# Public_CPU_Power.net
KiCad netlist of a schematic drawn in Altium Designer
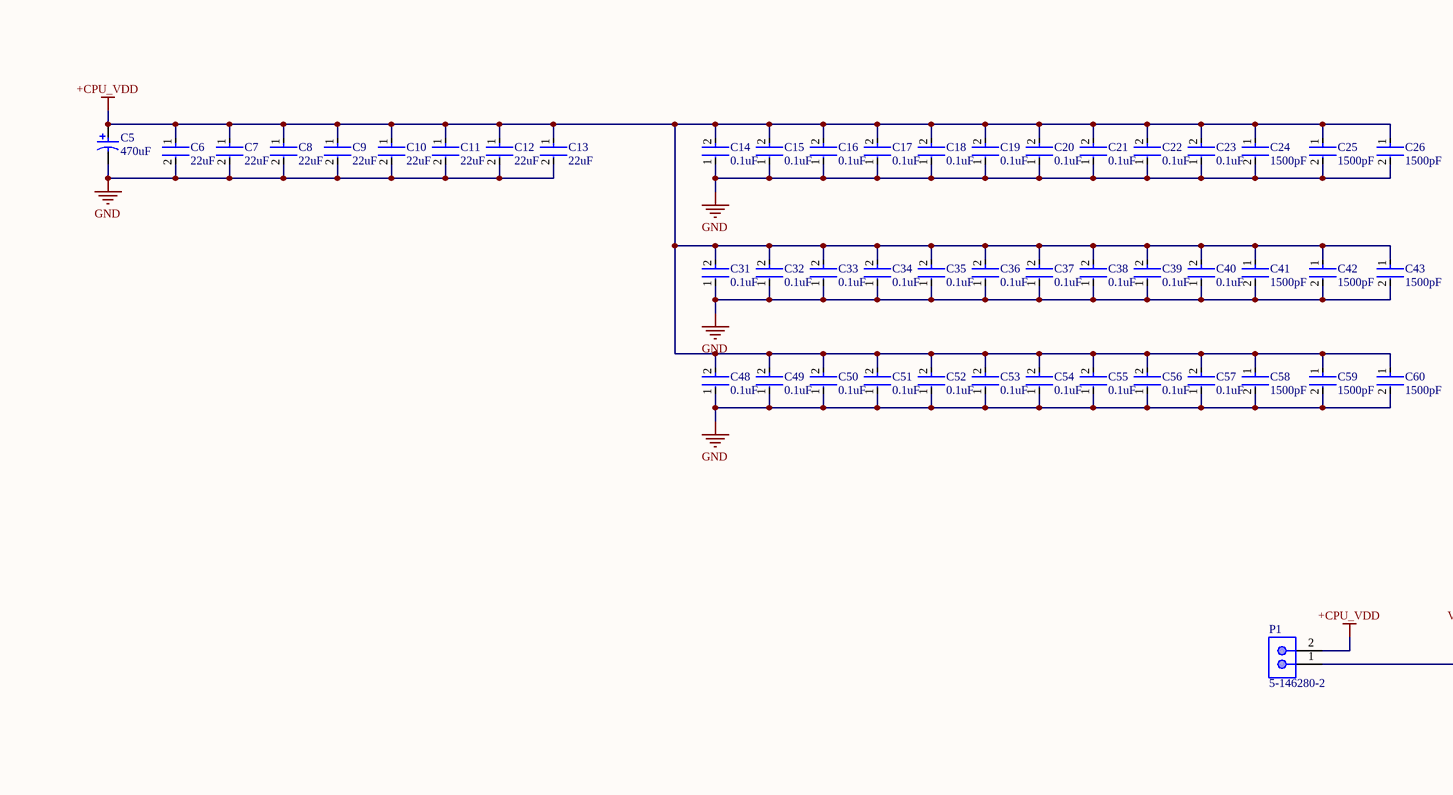
[diagram p0: Public_CPU_Power.SchDoc, top left]
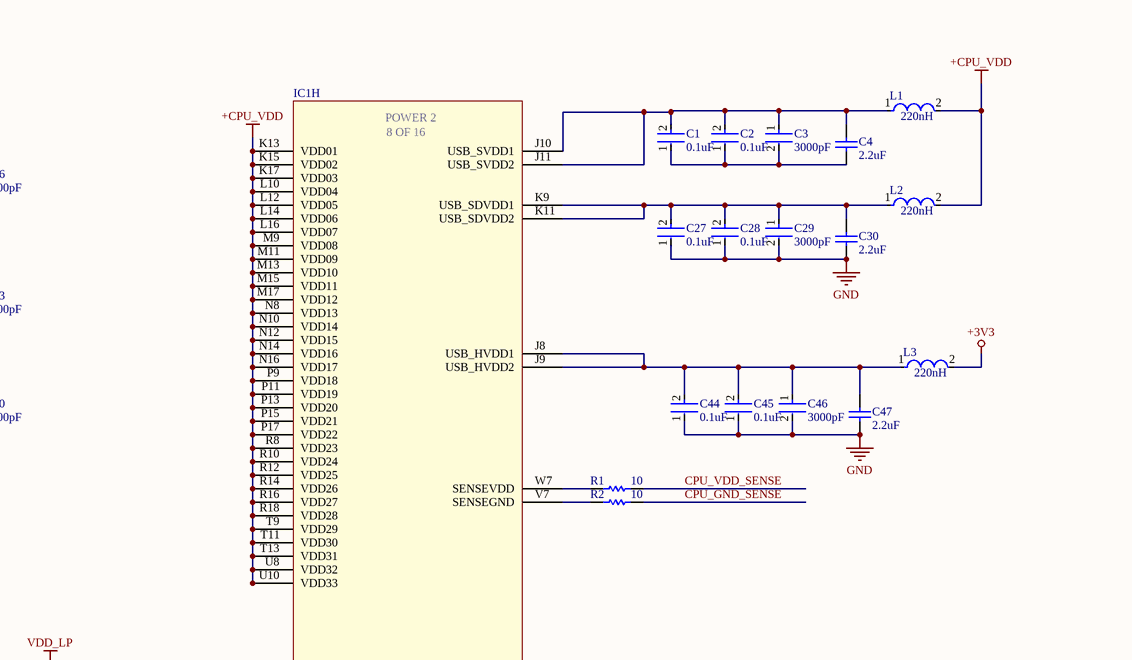
[diagram p1: Public_CPU_Power.SchDoc, top right]
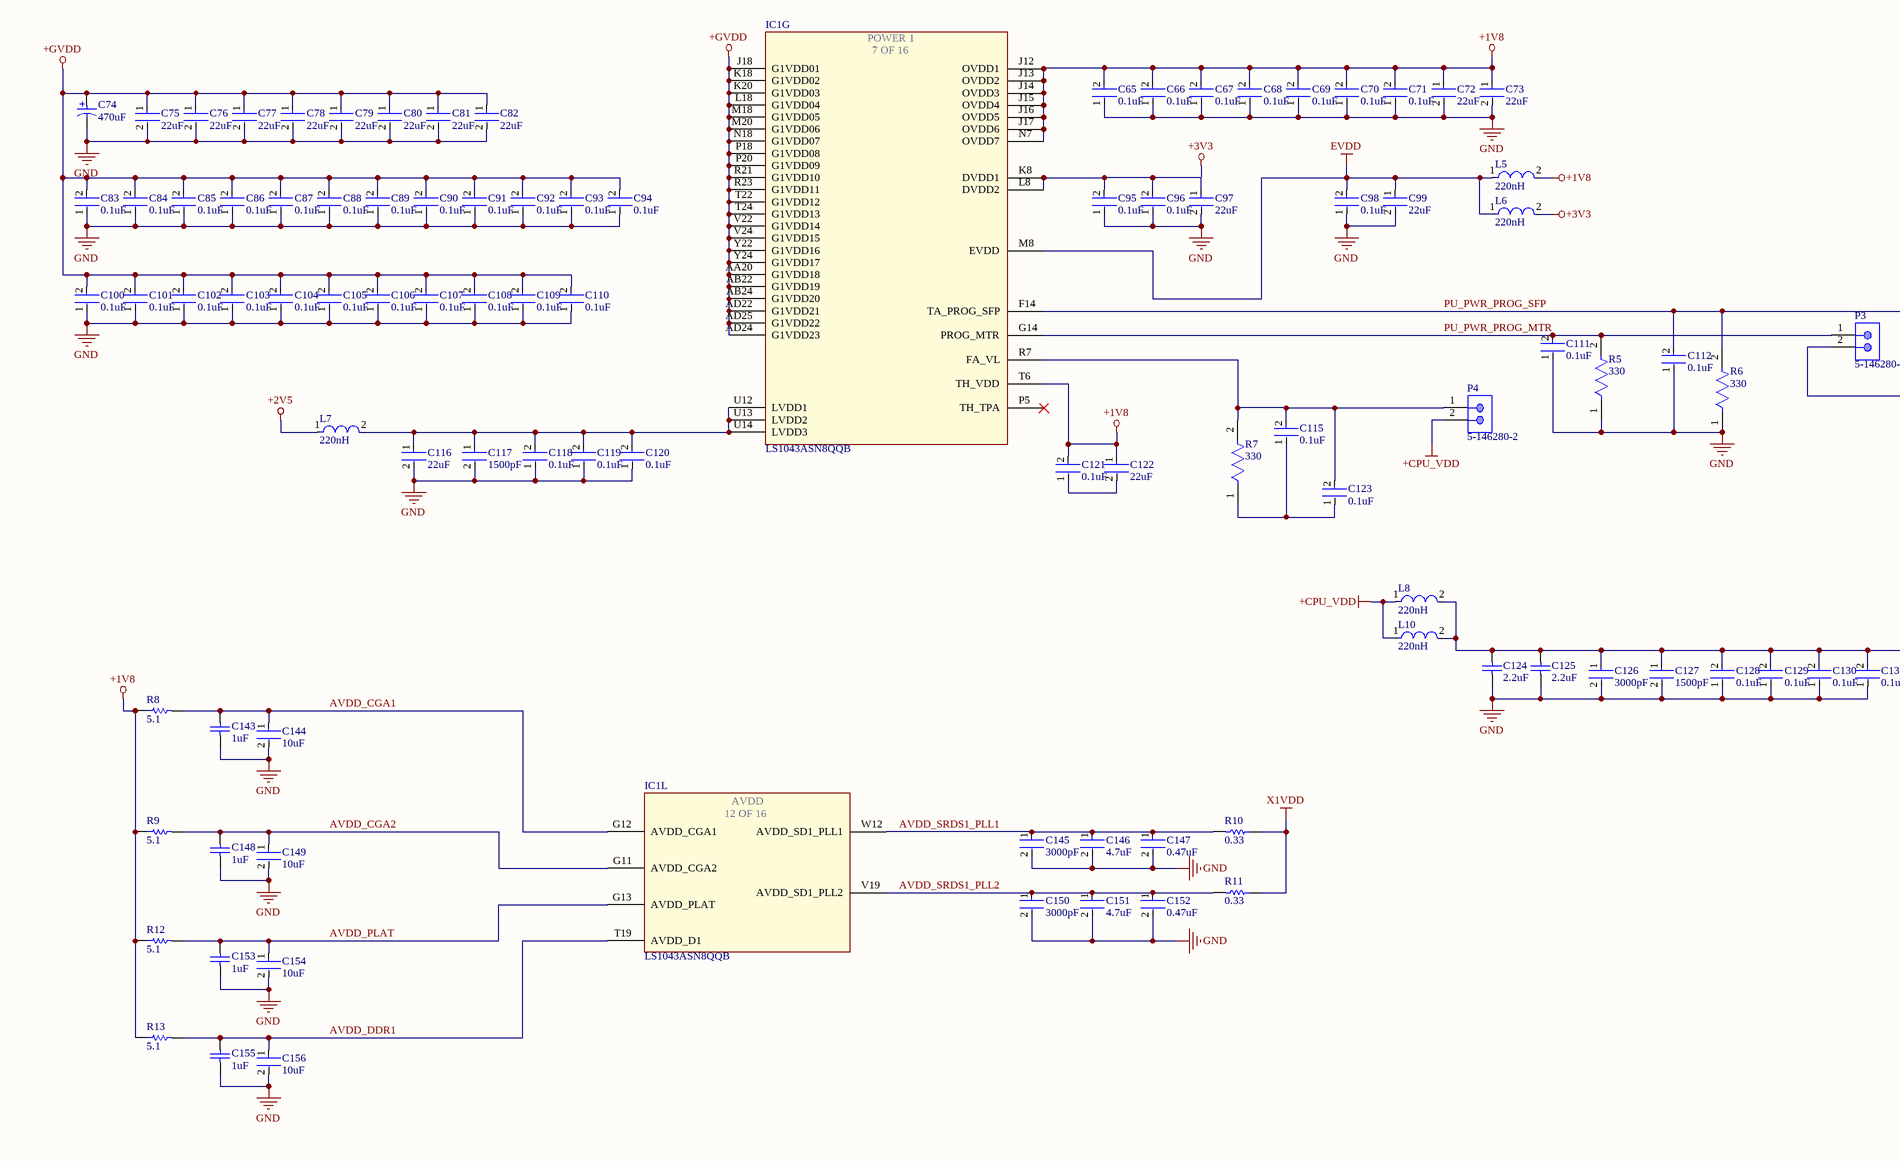
[diagram p2: Public_CPU_Power.SchDoc, bottom left]
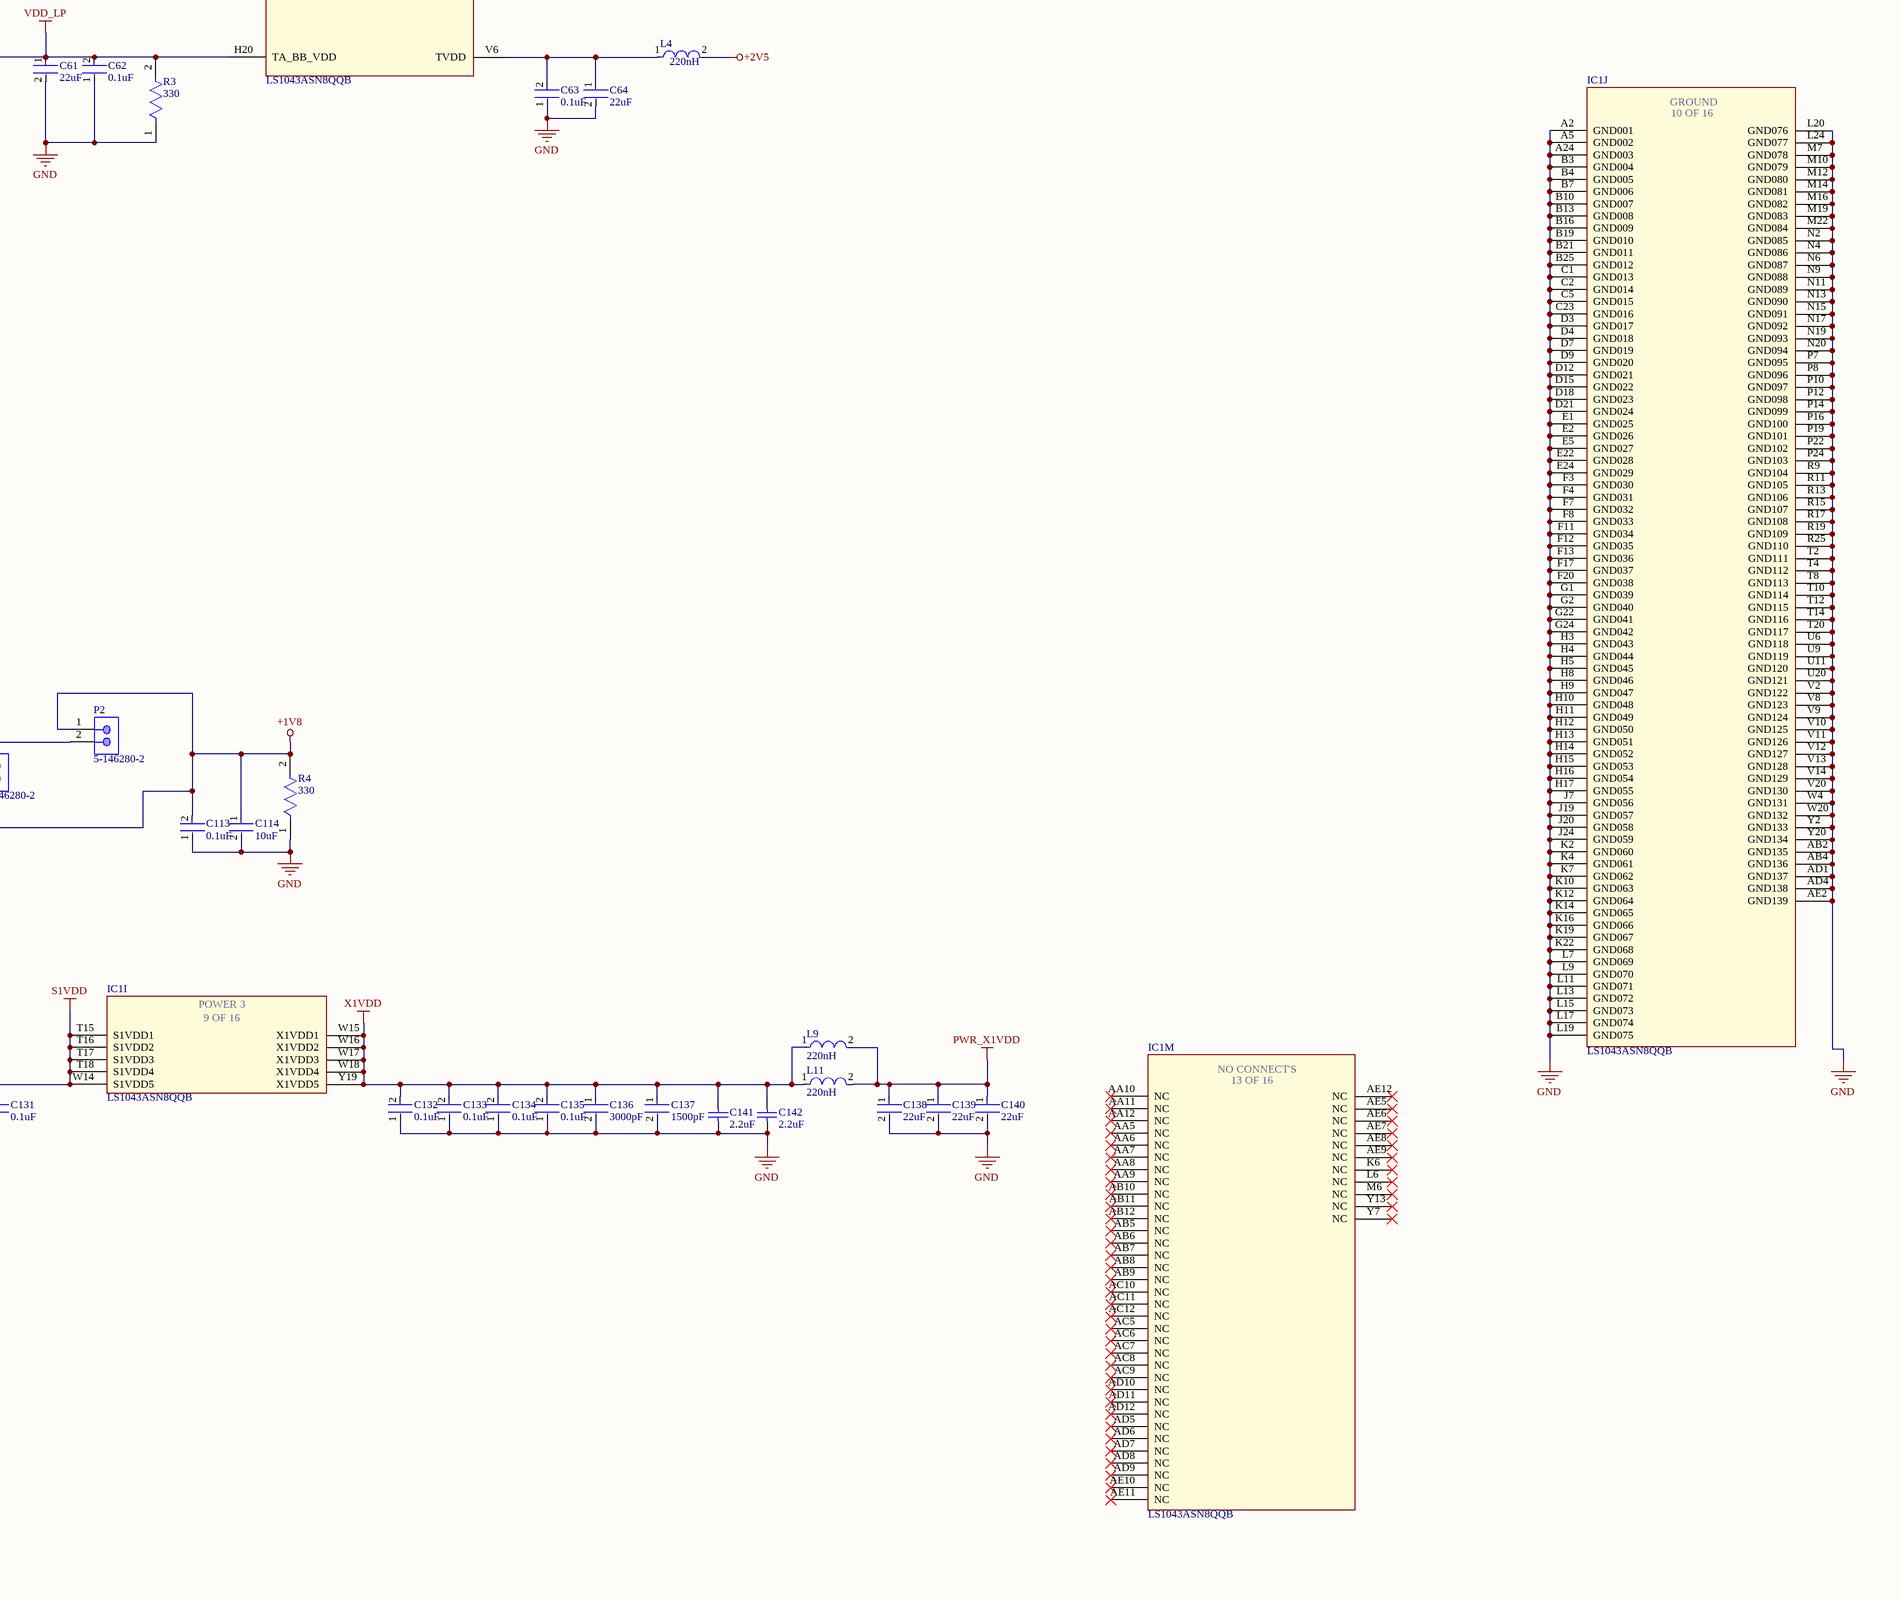
[diagram p3: Public_CPU_Power.SchDoc, bottom right]

(export (version "E")
  (design (tool "Eeschema 10.0.6"))
  (components
    (comp (ref "C1")
      (value "0.1uF")
      (footprint "FP-GRM15-MFG")
      (description "CAP CER 0.1UF 16V X7R 0402")
      (fields (field (name "MANUFACTURER PART NUMBER") "GRM155R71C104KA88D") (field (name "TOLERANCE") "10%"))
      (libsource (lib "Altium Content Vault") (part "236180d848d6139a670b325ea6854c9"))
    )
    (comp (ref "C2")
      (value "0.1uF")
      (footprint "FP-GRM15-MFG")
      (description "CAP CER 0.1UF 16V X7R 0402")
      (fields (field (name "MANUFACTURER PART NUMBER") "GRM155R71C104KA88D") (field (name "TOLERANCE") "10%"))
      (libsource (lib "Altium Content Vault") (part "236180d848d6139a670b325ea6854c9"))
    )
    (comp (ref "C3")
      (value "3000pF")
      (footprint "FP-GRM155-0_05-IPC_B")
      (description "Chip Multilayer Ceramic Capacitors for General Purpose, 0402, 3000pF, U2J, -750ppm/°C, 5%, 10V")
      (fields (field (name "TOLERANCE") "5%"))
      (libsource (lib "Altium Content Vault") (part "02cd4be3c70576c341d710602a673aa"))
    )
    (comp (ref "C4")
      (value "2.2uF")
      (footprint "CAPC1005X55X30NL05T10")
      (fields (field (name "MANUFACTURER") "Kemet") (field (name "PART NUMBER") "C0402C225M9PACTU"))
      (libsource (lib "Altium Content Vault") (part "CAP"))
    )
    (comp (ref "C5")
      (value "470uF")
      (footprint "PNSC-FK-V-F_V")
      (fields (field (name "MANUFACTURER") "Panasonic"))
      (libsource (lib "Altium Content Vault") (part "CAP-P-2"))
    )
    (comp (ref "C6")
      (value "22uF")
      (footprint "FP-GRM21B-0_15-MFG")
      (description "Chip Multilayer Ceramic Capacitors for General Purpose, 0805, 22uF, X5R, 15%, 20%, 6.3V")
      (fields (field (name "VOLTAGE") "6.3V") (field (name "TOLERANCE") "20%"))
      (libsource (lib "Altium Content Vault") (part "b4654b650e69147ec39a6b967a45e02"))
    )
    (comp (ref "C7")
      (value "22uF")
      (footprint "FP-GRM21B-0_15-MFG")
      (description "Chip Multilayer Ceramic Capacitors for General Purpose, 0805, 22uF, X5R, 15%, 20%, 6.3V")
      (fields (field (name "VOLTAGE") "6.3V") (field (name "TOLERANCE") "20%"))
      (libsource (lib "Altium Content Vault") (part "b4654b650e69147ec39a6b967a45e02"))
    )
    (comp (ref "C8")
      (value "22uF")
      (footprint "FP-GRM21B-0_15-MFG")
      (description "Chip Multilayer Ceramic Capacitors for General Purpose, 0805, 22uF, X5R, 15%, 20%, 6.3V")
      (fields (field (name "VOLTAGE") "6.3V") (field (name "TOLERANCE") "20%"))
      (libsource (lib "Altium Content Vault") (part "b4654b650e69147ec39a6b967a45e02"))
    )
    (comp (ref "C9")
      (value "22uF")
      (footprint "FP-GRM21B-0_15-MFG")
      (description "Chip Multilayer Ceramic Capacitors for General Purpose, 0805, 22uF, X5R, 15%, 20%, 6.3V")
      (fields (field (name "VOLTAGE") "6.3V") (field (name "TOLERANCE") "20%"))
      (libsource (lib "Altium Content Vault") (part "b4654b650e69147ec39a6b967a45e02"))
    )
    (comp (ref "C10")
      (value "22uF")
      (footprint "FP-GRM21B-0_15-MFG")
      (description "Chip Multilayer Ceramic Capacitors for General Purpose, 0805, 22uF, X5R, 15%, 20%, 6.3V")
      (fields (field (name "VOLTAGE") "6.3V") (field (name "TOLERANCE") "20%"))
      (libsource (lib "Altium Content Vault") (part "b4654b650e69147ec39a6b967a45e02"))
    )
    (comp (ref "C11")
      (value "22uF")
      (footprint "FP-GRM21B-0_15-MFG")
      (description "Chip Multilayer Ceramic Capacitors for General Purpose, 0805, 22uF, X5R, 15%, 20%, 6.3V")
      (fields (field (name "VOLTAGE") "6.3V") (field (name "TOLERANCE") "20%"))
      (libsource (lib "Altium Content Vault") (part "b4654b650e69147ec39a6b967a45e02"))
    )
    (comp (ref "C12")
      (value "22uF")
      (footprint "FP-GRM21B-0_15-MFG")
      (description "Chip Multilayer Ceramic Capacitors for General Purpose, 0805, 22uF, X5R, 15%, 20%, 6.3V")
      (fields (field (name "VOLTAGE") "6.3V") (field (name "TOLERANCE") "20%"))
      (libsource (lib "Altium Content Vault") (part "b4654b650e69147ec39a6b967a45e02"))
    )
    (comp (ref "C13")
      (value "22uF")
      (footprint "FP-GRM21B-0_15-MFG")
      (description "Chip Multilayer Ceramic Capacitors for General Purpose, 0805, 22uF, X5R, 15%, 20%, 6.3V")
      (fields (field (name "VOLTAGE") "6.3V") (field (name "TOLERANCE") "20%"))
      (libsource (lib "Altium Content Vault") (part "b4654b650e69147ec39a6b967a45e02"))
    )
    (comp (ref "C14")
      (value "0.1uF")
      (footprint "FP-GRM15-MFG")
      (description "CAP CER 0.1UF 16V X7R 0402")
      (fields (field (name "MANUFACTURER PART NUMBER") "GRM155R71C104KA88D") (field (name "TOLERANCE") "10%"))
      (libsource (lib "Altium Content Vault") (part "236180d848d6139a670b325ea6854c9"))
    )
    (comp (ref "C15")
      (value "0.1uF")
      (footprint "FP-GRM15-MFG")
      (description "CAP CER 0.1UF 16V X7R 0402")
      (fields (field (name "MANUFACTURER PART NUMBER") "GRM155R71C104KA88D") (field (name "TOLERANCE") "10%"))
      (libsource (lib "Altium Content Vault") (part "236180d848d6139a670b325ea6854c9"))
    )
    (comp (ref "C16")
      (value "0.1uF")
      (footprint "FP-GRM15-MFG")
      (description "CAP CER 0.1UF 16V X7R 0402")
      (fields (field (name "MANUFACTURER PART NUMBER") "GRM155R71C104KA88D") (field (name "TOLERANCE") "10%"))
      (libsource (lib "Altium Content Vault") (part "236180d848d6139a670b325ea6854c9"))
    )
    (comp (ref "C17")
      (value "0.1uF")
      (footprint "FP-GRM15-MFG")
      (description "CAP CER 0.1UF 16V X7R 0402")
      (fields (field (name "MANUFACTURER PART NUMBER") "GRM155R71C104KA88D") (field (name "TOLERANCE") "10%"))
      (libsource (lib "Altium Content Vault") (part "236180d848d6139a670b325ea6854c9"))
    )
    (comp (ref "C18")
      (value "0.1uF")
      (footprint "FP-GRM15-MFG")
      (description "CAP CER 0.1UF 16V X7R 0402")
      (fields (field (name "MANUFACTURER PART NUMBER") "GRM155R71C104KA88D") (field (name "TOLERANCE") "10%"))
      (libsource (lib "Altium Content Vault") (part "236180d848d6139a670b325ea6854c9"))
    )
    (comp (ref "C19")
      (value "0.1uF")
      (footprint "FP-GRM15-MFG")
      (description "CAP CER 0.1UF 16V X7R 0402")
      (fields (field (name "MANUFACTURER PART NUMBER") "GRM155R71C104KA88D") (field (name "TOLERANCE") "10%"))
      (libsource (lib "Altium Content Vault") (part "236180d848d6139a670b325ea6854c9"))
    )
    (comp (ref "C20")
      (value "0.1uF")
      (footprint "FP-GRM15-MFG")
      (description "CAP CER 0.1UF 16V X7R 0402")
      (fields (field (name "MANUFACTURER PART NUMBER") "GRM155R71C104KA88D") (field (name "TOLERANCE") "10%"))
      (libsource (lib "Altium Content Vault") (part "236180d848d6139a670b325ea6854c9"))
    )
    (comp (ref "C21")
      (value "0.1uF")
      (footprint "FP-GRM15-MFG")
      (description "CAP CER 0.1UF 16V X7R 0402")
      (fields (field (name "MANUFACTURER PART NUMBER") "GRM155R71C104KA88D") (field (name "TOLERANCE") "10%"))
      (libsource (lib "Altium Content Vault") (part "236180d848d6139a670b325ea6854c9"))
    )
    (comp (ref "C22")
      (value "0.1uF")
      (footprint "FP-GRM15-MFG")
      (description "CAP CER 0.1UF 16V X7R 0402")
      (fields (field (name "MANUFACTURER PART NUMBER") "GRM155R71C104KA88D") (field (name "TOLERANCE") "10%"))
      (libsource (lib "Altium Content Vault") (part "236180d848d6139a670b325ea6854c9"))
    )
    (comp (ref "C23")
      (value "0.1uF")
      (footprint "FP-GRM15-MFG")
      (description "CAP CER 0.1UF 16V X7R 0402")
      (fields (field (name "MANUFACTURER PART NUMBER") "GRM155R71C104KA88D") (field (name "TOLERANCE") "10%"))
      (libsource (lib "Altium Content Vault") (part "236180d848d6139a670b325ea6854c9"))
    )
    (comp (ref "C24")
      (value "1500pF")
      (footprint "FP-C0402-BB-MFG")
      (description "CAP CER 1500PF 50V X7R 0402")
      (fields
        (field (name "OCTOPART") "https://octopart.com/c0402c152k5ractu-kemet-125298")
        (field (name "TOLERANCE") "0.1")
      )
      (libsource (lib "Altium Content Vault") (part "b4654b650e69147ec39a6b967a45e02"))
    )
    (comp (ref "C25")
      (value "1500pF")
      (footprint "FP-C0402-BB-MFG")
      (description "CAP CER 1500PF 50V X7R 0402")
      (fields
        (field (name "OCTOPART") "https://octopart.com/c0402c152k5ractu-kemet-125298")
        (field (name "TOLERANCE") "0.1")
      )
      (libsource (lib "Altium Content Vault") (part "b4654b650e69147ec39a6b967a45e02"))
    )
    (comp (ref "C26")
      (value "1500pF")
      (footprint "FP-C0402-BB-MFG")
      (description "CAP CER 1500PF 50V X7R 0402")
      (fields
        (field (name "OCTOPART") "https://octopart.com/c0402c152k5ractu-kemet-125298")
        (field (name "TOLERANCE") "0.1")
      )
      (libsource (lib "Altium Content Vault") (part "b4654b650e69147ec39a6b967a45e02"))
    )
    (comp (ref "C27")
      (value "0.1uF")
      (footprint "FP-GRM15-MFG")
      (description "CAP CER 0.1UF 16V X7R 0402")
      (fields (field (name "MANUFACTURER PART NUMBER") "GRM155R71C104KA88D") (field (name "TOLERANCE") "10%"))
      (libsource (lib "Altium Content Vault") (part "236180d848d6139a670b325ea6854c9"))
    )
    (comp (ref "C28")
      (value "0.1uF")
      (footprint "FP-GRM15-MFG")
      (description "CAP CER 0.1UF 16V X7R 0402")
      (fields (field (name "MANUFACTURER PART NUMBER") "GRM155R71C104KA88D") (field (name "TOLERANCE") "10%"))
      (libsource (lib "Altium Content Vault") (part "236180d848d6139a670b325ea6854c9"))
    )
    (comp (ref "C29")
      (value "3000pF")
      (footprint "FP-GRM155-0_05-IPC_B")
      (description "Chip Multilayer Ceramic Capacitors for General Purpose, 0402, 3000pF, U2J, -750ppm/°C, 5%, 10V")
      (fields (field (name "TOLERANCE") "5%"))
      (libsource (lib "Altium Content Vault") (part "02cd4be3c70576c341d710602a673aa"))
    )
    (comp (ref "C30")
      (value "2.2uF")
      (footprint "CAPC1005X55X30NL05T10")
      (fields (field (name "MANUFACTURER") "Kemet") (field (name "PART NUMBER") "C0402C225M9PACTU"))
      (libsource (lib "Altium Content Vault") (part "CAP"))
    )
    (comp (ref "C31")
      (value "0.1uF")
      (footprint "FP-GRM15-MFG")
      (description "CAP CER 0.1UF 16V X7R 0402")
      (fields (field (name "MANUFACTURER PART NUMBER") "GRM155R71C104KA88D") (field (name "TOLERANCE") "10%"))
      (libsource (lib "Altium Content Vault") (part "236180d848d6139a670b325ea6854c9"))
    )
    (comp (ref "C32")
      (value "0.1uF")
      (footprint "FP-GRM15-MFG")
      (description "CAP CER 0.1UF 16V X7R 0402")
      (fields (field (name "MANUFACTURER PART NUMBER") "GRM155R71C104KA88D") (field (name "TOLERANCE") "10%"))
      (libsource (lib "Altium Content Vault") (part "236180d848d6139a670b325ea6854c9"))
    )
    (comp (ref "C33")
      (value "0.1uF")
      (footprint "FP-GRM15-MFG")
      (description "CAP CER 0.1UF 16V X7R 0402")
      (fields (field (name "MANUFACTURER PART NUMBER") "GRM155R71C104KA88D") (field (name "TOLERANCE") "10%"))
      (libsource (lib "Altium Content Vault") (part "236180d848d6139a670b325ea6854c9"))
    )
    (comp (ref "C34")
      (value "0.1uF")
      (footprint "FP-GRM15-MFG")
      (description "CAP CER 0.1UF 16V X7R 0402")
      (fields (field (name "MANUFACTURER PART NUMBER") "GRM155R71C104KA88D") (field (name "TOLERANCE") "10%"))
      (libsource (lib "Altium Content Vault") (part "236180d848d6139a670b325ea6854c9"))
    )
    (comp (ref "C35")
      (value "0.1uF")
      (footprint "FP-GRM15-MFG")
      (description "CAP CER 0.1UF 16V X7R 0402")
      (fields (field (name "MANUFACTURER PART NUMBER") "GRM155R71C104KA88D") (field (name "TOLERANCE") "10%"))
      (libsource (lib "Altium Content Vault") (part "236180d848d6139a670b325ea6854c9"))
    )
    (comp (ref "C36")
      (value "0.1uF")
      (footprint "FP-GRM15-MFG")
      (description "CAP CER 0.1UF 16V X7R 0402")
      (fields (field (name "MANUFACTURER PART NUMBER") "GRM155R71C104KA88D") (field (name "TOLERANCE") "10%"))
      (libsource (lib "Altium Content Vault") (part "236180d848d6139a670b325ea6854c9"))
    )
    (comp (ref "C37")
      (value "0.1uF")
      (footprint "FP-GRM15-MFG")
      (description "CAP CER 0.1UF 16V X7R 0402")
      (fields (field (name "MANUFACTURER PART NUMBER") "GRM155R71C104KA88D") (field (name "TOLERANCE") "10%"))
      (libsource (lib "Altium Content Vault") (part "236180d848d6139a670b325ea6854c9"))
    )
    (comp (ref "C38")
      (value "0.1uF")
      (footprint "FP-GRM15-MFG")
      (description "CAP CER 0.1UF 16V X7R 0402")
      (fields (field (name "MANUFACTURER PART NUMBER") "GRM155R71C104KA88D") (field (name "TOLERANCE") "10%"))
      (libsource (lib "Altium Content Vault") (part "236180d848d6139a670b325ea6854c9"))
    )
    (comp (ref "C39")
      (value "0.1uF")
      (footprint "FP-GRM15-MFG")
      (description "CAP CER 0.1UF 16V X7R 0402")
      (fields (field (name "MANUFACTURER PART NUMBER") "GRM155R71C104KA88D") (field (name "TOLERANCE") "10%"))
      (libsource (lib "Altium Content Vault") (part "236180d848d6139a670b325ea6854c9"))
    )
    (comp (ref "C40")
      (value "0.1uF")
      (footprint "FP-GRM15-MFG")
      (description "CAP CER 0.1UF 16V X7R 0402")
      (fields (field (name "MANUFACTURER PART NUMBER") "GRM155R71C104KA88D") (field (name "TOLERANCE") "10%"))
      (libsource (lib "Altium Content Vault") (part "236180d848d6139a670b325ea6854c9"))
    )
    (comp (ref "C41")
      (value "1500pF")
      (footprint "FP-C0402-BB-MFG")
      (description "CAP CER 1500PF 50V X7R 0402")
      (fields
        (field (name "OCTOPART") "https://octopart.com/c0402c152k5ractu-kemet-125298")
        (field (name "TOLERANCE") "0.1")
      )
      (libsource (lib "Altium Content Vault") (part "b4654b650e69147ec39a6b967a45e02"))
    )
    (comp (ref "C42")
      (value "1500pF")
      (footprint "FP-C0402-BB-MFG")
      (description "CAP CER 1500PF 50V X7R 0402")
      (fields
        (field (name "OCTOPART") "https://octopart.com/c0402c152k5ractu-kemet-125298")
        (field (name "TOLERANCE") "0.1")
      )
      (libsource (lib "Altium Content Vault") (part "b4654b650e69147ec39a6b967a45e02"))
    )
    (comp (ref "C43")
      (value "1500pF")
      (footprint "FP-C0402-BB-MFG")
      (description "CAP CER 1500PF 50V X7R 0402")
      (fields
        (field (name "OCTOPART") "https://octopart.com/c0402c152k5ractu-kemet-125298")
        (field (name "TOLERANCE") "0.1")
      )
      (libsource (lib "Altium Content Vault") (part "b4654b650e69147ec39a6b967a45e02"))
    )
    (comp (ref "C44")
      (value "0.1uF")
      (footprint "FP-GRM15-MFG")
      (description "CAP CER 0.1UF 16V X7R 0402")
      (fields (field (name "MANUFACTURER PART NUMBER") "GRM155R71C104KA88D") (field (name "TOLERANCE") "10%"))
      (libsource (lib "Altium Content Vault") (part "236180d848d6139a670b325ea6854c9"))
    )
    (comp (ref "C45")
      (value "0.1uF")
      (footprint "FP-GRM15-MFG")
      (description "CAP CER 0.1UF 16V X7R 0402")
      (fields (field (name "MANUFACTURER PART NUMBER") "GRM155R71C104KA88D") (field (name "TOLERANCE") "10%"))
      (libsource (lib "Altium Content Vault") (part "236180d848d6139a670b325ea6854c9"))
    )
    (comp (ref "C46")
      (value "3000pF")
      (footprint "FP-GRM155-0_05-IPC_B")
      (description "Chip Multilayer Ceramic Capacitors for General Purpose, 0402, 3000pF, U2J, -750ppm/°C, 5%, 10V")
      (fields (field (name "TOLERANCE") "5%"))
      (libsource (lib "Altium Content Vault") (part "02cd4be3c70576c341d710602a673aa"))
    )
    (comp (ref "C47")
      (value "2.2uF")
      (footprint "CAPC1005X55X30NL05T10")
      (fields (field (name "MANUFACTURER") "Kemet") (field (name "PART NUMBER") "C0402C225M9PACTU"))
      (libsource (lib "Altium Content Vault") (part "CAP"))
    )
    (comp (ref "C48")
      (value "0.1uF")
      (footprint "FP-GRM15-MFG")
      (description "CAP CER 0.1UF 16V X7R 0402")
      (fields (field (name "MANUFACTURER PART NUMBER") "GRM155R71C104KA88D") (field (name "TOLERANCE") "10%"))
      (libsource (lib "Altium Content Vault") (part "236180d848d6139a670b325ea6854c9"))
    )
    (comp (ref "C49")
      (value "0.1uF")
      (footprint "FP-GRM15-MFG")
      (description "CAP CER 0.1UF 16V X7R 0402")
      (fields (field (name "MANUFACTURER PART NUMBER") "GRM155R71C104KA88D") (field (name "TOLERANCE") "10%"))
      (libsource (lib "Altium Content Vault") (part "236180d848d6139a670b325ea6854c9"))
    )
    (comp (ref "C50")
      (value "0.1uF")
      (footprint "FP-GRM15-MFG")
      (description "CAP CER 0.1UF 16V X7R 0402")
      (fields (field (name "MANUFACTURER PART NUMBER") "GRM155R71C104KA88D") (field (name "TOLERANCE") "10%"))
      (libsource (lib "Altium Content Vault") (part "236180d848d6139a670b325ea6854c9"))
    )
    (comp (ref "C51")
      (value "0.1uF")
      (footprint "FP-GRM15-MFG")
      (description "CAP CER 0.1UF 16V X7R 0402")
      (fields (field (name "MANUFACTURER PART NUMBER") "GRM155R71C104KA88D") (field (name "TOLERANCE") "10%"))
      (libsource (lib "Altium Content Vault") (part "236180d848d6139a670b325ea6854c9"))
    )
    (comp (ref "C52")
      (value "0.1uF")
      (footprint "FP-GRM15-MFG")
      (description "CAP CER 0.1UF 16V X7R 0402")
      (fields (field (name "MANUFACTURER PART NUMBER") "GRM155R71C104KA88D") (field (name "TOLERANCE") "10%"))
      (libsource (lib "Altium Content Vault") (part "236180d848d6139a670b325ea6854c9"))
    )
    (comp (ref "C53")
      (value "0.1uF")
      (footprint "FP-GRM15-MFG")
      (description "CAP CER 0.1UF 16V X7R 0402")
      (fields (field (name "MANUFACTURER PART NUMBER") "GRM155R71C104KA88D") (field (name "TOLERANCE") "10%"))
      (libsource (lib "Altium Content Vault") (part "236180d848d6139a670b325ea6854c9"))
    )
    (comp (ref "C54")
      (value "0.1uF")
      (footprint "FP-GRM15-MFG")
      (description "CAP CER 0.1UF 16V X7R 0402")
      (fields (field (name "MANUFACTURER PART NUMBER") "GRM155R71C104KA88D") (field (name "TOLERANCE") "10%"))
      (libsource (lib "Altium Content Vault") (part "236180d848d6139a670b325ea6854c9"))
    )
    (comp (ref "C55")
      (value "0.1uF")
      (footprint "FP-GRM15-MFG")
      (description "CAP CER 0.1UF 16V X7R 0402")
      (fields (field (name "MANUFACTURER PART NUMBER") "GRM155R71C104KA88D") (field (name "TOLERANCE") "10%"))
      (libsource (lib "Altium Content Vault") (part "236180d848d6139a670b325ea6854c9"))
    )
    (comp (ref "C56")
      (value "0.1uF")
      (footprint "FP-GRM15-MFG")
      (description "CAP CER 0.1UF 16V X7R 0402")
      (fields (field (name "MANUFACTURER PART NUMBER") "GRM155R71C104KA88D") (field (name "TOLERANCE") "10%"))
      (libsource (lib "Altium Content Vault") (part "236180d848d6139a670b325ea6854c9"))
    )
    (comp (ref "C57")
      (value "0.1uF")
      (footprint "FP-GRM15-MFG")
      (description "CAP CER 0.1UF 16V X7R 0402")
      (fields (field (name "MANUFACTURER PART NUMBER") "GRM155R71C104KA88D") (field (name "TOLERANCE") "10%"))
      (libsource (lib "Altium Content Vault") (part "236180d848d6139a670b325ea6854c9"))
    )
    (comp (ref "C58")
      (value "1500pF")
      (footprint "FP-C0402-BB-MFG")
      (description "CAP CER 1500PF 50V X7R 0402")
      (fields
        (field (name "OCTOPART") "https://octopart.com/c0402c152k5ractu-kemet-125298")
        (field (name "TOLERANCE") "0.1")
      )
      (libsource (lib "Altium Content Vault") (part "b4654b650e69147ec39a6b967a45e02"))
    )
    (comp (ref "C59")
      (value "1500pF")
      (footprint "FP-C0402-BB-MFG")
      (description "CAP CER 1500PF 50V X7R 0402")
      (fields
        (field (name "OCTOPART") "https://octopart.com/c0402c152k5ractu-kemet-125298")
        (field (name "TOLERANCE") "0.1")
      )
      (libsource (lib "Altium Content Vault") (part "b4654b650e69147ec39a6b967a45e02"))
    )
    (comp (ref "C60")
      (value "1500pF")
      (footprint "FP-C0402-BB-MFG")
      (description "CAP CER 1500PF 50V X7R 0402")
      (fields
        (field (name "OCTOPART") "https://octopart.com/c0402c152k5ractu-kemet-125298")
        (field (name "TOLERANCE") "0.1")
      )
      (libsource (lib "Altium Content Vault") (part "b4654b650e69147ec39a6b967a45e02"))
    )
    (comp (ref "C61")
      (value "22uF")
      (footprint "FP-GRM21B-0_15-MFG")
      (description "Chip Multilayer Ceramic Capacitors for General Purpose, 0805, 22uF, X5R, 15%, 20%, 6.3V")
      (fields (field (name "VOLTAGE") "6.3V") (field (name "TOLERANCE") "20%"))
      (libsource (lib "Altium Content Vault") (part "b4654b650e69147ec39a6b967a45e02"))
    )
    (comp (ref "C62")
      (value "0.1uF")
      (footprint "FP-GRM15-MFG")
      (description "CAP CER 0.1UF 16V X7R 0402")
      (fields (field (name "MANUFACTURER PART NUMBER") "GRM155R71C104KA88D") (field (name "TOLERANCE") "10%"))
      (libsource (lib "Altium Content Vault") (part "236180d848d6139a670b325ea6854c9"))
    )
    (comp (ref "C63")
      (value "0.1uF")
      (footprint "FP-GRM15-MFG")
      (description "CAP CER 0.1UF 16V X7R 0402")
      (fields (field (name "MANUFACTURER PART NUMBER") "GRM155R71C104KA88D") (field (name "TOLERANCE") "10%"))
      (libsource (lib "Altium Content Vault") (part "236180d848d6139a670b325ea6854c9"))
    )
    (comp (ref "C64")
      (value "22uF")
      (footprint "FP-GRM21B-0_15-MFG")
      (description "Chip Multilayer Ceramic Capacitors for General Purpose, 0805, 22uF, X5R, 15%, 20%, 6.3V")
      (fields (field (name "VOLTAGE") "6.3V") (field (name "TOLERANCE") "20%"))
      (libsource (lib "Altium Content Vault") (part "b4654b650e69147ec39a6b967a45e02"))
    )
    (comp (ref "C65")
      (value "0.1uF")
      (footprint "FP-GRM15-MFG")
      (description "CAP CER 0.1UF 16V X7R 0402")
      (fields (field (name "MANUFACTURER PART NUMBER") "GRM155R71C104KA88D") (field (name "TOLERANCE") "10%"))
      (libsource (lib "Altium Content Vault") (part "236180d848d6139a670b325ea6854c9"))
    )
    (comp (ref "C66")
      (value "0.1uF")
      (footprint "FP-GRM15-MFG")
      (description "CAP CER 0.1UF 16V X7R 0402")
      (fields (field (name "MANUFACTURER PART NUMBER") "GRM155R71C104KA88D") (field (name "TOLERANCE") "10%"))
      (libsource (lib "Altium Content Vault") (part "236180d848d6139a670b325ea6854c9"))
    )
    (comp (ref "C67")
      (value "0.1uF")
      (footprint "FP-GRM15-MFG")
      (description "CAP CER 0.1UF 16V X7R 0402")
      (fields (field (name "MANUFACTURER PART NUMBER") "GRM155R71C104KA88D") (field (name "TOLERANCE") "10%"))
      (libsource (lib "Altium Content Vault") (part "236180d848d6139a670b325ea6854c9"))
    )
    (comp (ref "C68")
      (value "0.1uF")
      (footprint "FP-GRM15-MFG")
      (description "CAP CER 0.1UF 16V X7R 0402")
      (fields (field (name "MANUFACTURER PART NUMBER") "GRM155R71C104KA88D") (field (name "TOLERANCE") "10%"))
      (libsource (lib "Altium Content Vault") (part "236180d848d6139a670b325ea6854c9"))
    )
    (comp (ref "C69")
      (value "0.1uF")
      (footprint "FP-GRM15-MFG")
      (description "CAP CER 0.1UF 16V X7R 0402")
      (fields (field (name "MANUFACTURER PART NUMBER") "GRM155R71C104KA88D") (field (name "TOLERANCE") "10%"))
      (libsource (lib "Altium Content Vault") (part "236180d848d6139a670b325ea6854c9"))
    )
    (comp (ref "C70")
      (value "0.1uF")
      (footprint "FP-GRM15-MFG")
      (description "CAP CER 0.1UF 16V X7R 0402")
      (fields (field (name "MANUFACTURER PART NUMBER") "GRM155R71C104KA88D") (field (name "TOLERANCE") "10%"))
      (libsource (lib "Altium Content Vault") (part "236180d848d6139a670b325ea6854c9"))
    )
    (comp (ref "C71")
      (value "0.1uF")
      (footprint "FP-GRM15-MFG")
      (description "CAP CER 0.1UF 16V X7R 0402")
      (fields (field (name "MANUFACTURER PART NUMBER") "GRM155R71C104KA88D") (field (name "TOLERANCE") "10%"))
      (libsource (lib "Altium Content Vault") (part "236180d848d6139a670b325ea6854c9"))
    )
    (comp (ref "C72")
      (value "22uF")
      (footprint "FP-GRM21B-0_15-MFG")
      (description "Chip Multilayer Ceramic Capacitors for General Purpose, 0805, 22uF, X5R, 15%, 20%, 6.3V")
      (fields (field (name "VOLTAGE") "6.3V") (field (name "TOLERANCE") "20%"))
      (libsource (lib "Altium Content Vault") (part "b4654b650e69147ec39a6b967a45e02"))
    )
    (comp (ref "C73")
      (value "22uF")
      (footprint "FP-GRM21B-0_15-MFG")
      (description "Chip Multilayer Ceramic Capacitors for General Purpose, 0805, 22uF, X5R, 15%, 20%, 6.3V")
      (fields (field (name "VOLTAGE") "6.3V") (field (name "TOLERANCE") "20%"))
      (libsource (lib "Altium Content Vault") (part "b4654b650e69147ec39a6b967a45e02"))
    )
    (comp (ref "C74")
      (value "470uF")
      (footprint "PNSC-FK-V-F_V")
      (fields (field (name "MANUFACTURER") "Panasonic"))
      (libsource (lib "Altium Content Vault") (part "CAP-P-2"))
    )
    (comp (ref "C75")
      (value "22uF")
      (footprint "FP-GRM21B-0_15-MFG")
      (description "Chip Multilayer Ceramic Capacitors for General Purpose, 0805, 22uF, X5R, 15%, 20%, 6.3V")
      (fields (field (name "VOLTAGE") "6.3V") (field (name "TOLERANCE") "20%"))
      (libsource (lib "Altium Content Vault") (part "b4654b650e69147ec39a6b967a45e02"))
    )
    (comp (ref "C76")
      (value "22uF")
      (footprint "FP-GRM21B-0_15-MFG")
      (description "Chip Multilayer Ceramic Capacitors for General Purpose, 0805, 22uF, X5R, 15%, 20%, 6.3V")
      (fields (field (name "VOLTAGE") "6.3V") (field (name "TOLERANCE") "20%"))
      (libsource (lib "Altium Content Vault") (part "b4654b650e69147ec39a6b967a45e02"))
    )
    (comp (ref "C77")
      (value "22uF")
      (footprint "FP-GRM21B-0_15-MFG")
      (description "Chip Multilayer Ceramic Capacitors for General Purpose, 0805, 22uF, X5R, 15%, 20%, 6.3V")
      (fields (field (name "VOLTAGE") "6.3V") (field (name "TOLERANCE") "20%"))
      (libsource (lib "Altium Content Vault") (part "b4654b650e69147ec39a6b967a45e02"))
    )
    (comp (ref "C78")
      (value "22uF")
      (footprint "FP-GRM21B-0_15-MFG")
      (description "Chip Multilayer Ceramic Capacitors for General Purpose, 0805, 22uF, X5R, 15%, 20%, 6.3V")
      (fields (field (name "VOLTAGE") "6.3V") (field (name "TOLERANCE") "20%"))
      (libsource (lib "Altium Content Vault") (part "b4654b650e69147ec39a6b967a45e02"))
    )
    (comp (ref "C79")
      (value "22uF")
      (footprint "FP-GRM21B-0_15-MFG")
      (description "Chip Multilayer Ceramic Capacitors for General Purpose, 0805, 22uF, X5R, 15%, 20%, 6.3V")
      (fields (field (name "VOLTAGE") "6.3V") (field (name "TOLERANCE") "20%"))
      (libsource (lib "Altium Content Vault") (part "b4654b650e69147ec39a6b967a45e02"))
    )
    (comp (ref "C80")
      (value "22uF")
      (footprint "FP-GRM21B-0_15-MFG")
      (description "Chip Multilayer Ceramic Capacitors for General Purpose, 0805, 22uF, X5R, 15%, 20%, 6.3V")
      (fields (field (name "VOLTAGE") "6.3V") (field (name "TOLERANCE") "20%"))
      (libsource (lib "Altium Content Vault") (part "b4654b650e69147ec39a6b967a45e02"))
    )
    (comp (ref "C81")
      (value "22uF")
      (footprint "FP-GRM21B-0_15-MFG")
      (description "Chip Multilayer Ceramic Capacitors for General Purpose, 0805, 22uF, X5R, 15%, 20%, 6.3V")
      (fields (field (name "VOLTAGE") "6.3V") (field (name "TOLERANCE") "20%"))
      (libsource (lib "Altium Content Vault") (part "b4654b650e69147ec39a6b967a45e02"))
    )
    (comp (ref "C82")
      (value "22uF")
      (footprint "FP-GRM21B-0_15-MFG")
      (description "Chip Multilayer Ceramic Capacitors for General Purpose, 0805, 22uF, X5R, 15%, 20%, 6.3V")
      (fields (field (name "VOLTAGE") "6.3V") (field (name "TOLERANCE") "20%"))
      (libsource (lib "Altium Content Vault") (part "b4654b650e69147ec39a6b967a45e02"))
    )
    (comp (ref "C83")
      (value "0.1uF")
      (footprint "FP-GRM15-MFG")
      (description "CAP CER 0.1UF 16V X7R 0402")
      (fields (field (name "MANUFACTURER PART NUMBER") "GRM155R71C104KA88D") (field (name "TOLERANCE") "10%"))
      (libsource (lib "Altium Content Vault") (part "236180d848d6139a670b325ea6854c9"))
    )
    (comp (ref "C84")
      (value "0.1uF")
      (footprint "FP-GRM15-MFG")
      (description "CAP CER 0.1UF 16V X7R 0402")
      (fields (field (name "MANUFACTURER PART NUMBER") "GRM155R71C104KA88D") (field (name "TOLERANCE") "10%"))
      (libsource (lib "Altium Content Vault") (part "236180d848d6139a670b325ea6854c9"))
    )
    (comp (ref "C85")
      (value "0.1uF")
      (footprint "FP-GRM15-MFG")
      (description "CAP CER 0.1UF 16V X7R 0402")
      (fields (field (name "MANUFACTURER PART NUMBER") "GRM155R71C104KA88D") (field (name "TOLERANCE") "10%"))
      (libsource (lib "Altium Content Vault") (part "236180d848d6139a670b325ea6854c9"))
    )
    (comp (ref "C86")
      (value "0.1uF")
      (footprint "FP-GRM15-MFG")
      (description "CAP CER 0.1UF 16V X7R 0402")
      (fields (field (name "MANUFACTURER PART NUMBER") "GRM155R71C104KA88D") (field (name "TOLERANCE") "10%"))
      (libsource (lib "Altium Content Vault") (part "236180d848d6139a670b325ea6854c9"))
    )
    (comp (ref "C87")
      (value "0.1uF")
      (footprint "FP-GRM15-MFG")
      (description "CAP CER 0.1UF 16V X7R 0402")
      (fields (field (name "MANUFACTURER PART NUMBER") "GRM155R71C104KA88D") (field (name "TOLERANCE") "10%"))
      (libsource (lib "Altium Content Vault") (part "236180d848d6139a670b325ea6854c9"))
    )
    (comp (ref "C88")
      (value "0.1uF")
      (footprint "FP-GRM15-MFG")
      (description "CAP CER 0.1UF 16V X7R 0402")
      (fields (field (name "MANUFACTURER PART NUMBER") "GRM155R71C104KA88D") (field (name "TOLERANCE") "10%"))
      (libsource (lib "Altium Content Vault") (part "236180d848d6139a670b325ea6854c9"))
    )
    (comp (ref "C89")
      (value "0.1uF")
      (footprint "FP-GRM15-MFG")
      (description "CAP CER 0.1UF 16V X7R 0402")
      (fields (field (name "MANUFACTURER PART NUMBER") "GRM155R71C104KA88D") (field (name "TOLERANCE") "10%"))
      (libsource (lib "Altium Content Vault") (part "236180d848d6139a670b325ea6854c9"))
    )
    (comp (ref "C90")
      (value "0.1uF")
      (footprint "FP-GRM15-MFG")
      (description "CAP CER 0.1UF 16V X7R 0402")
      (fields (field (name "MANUFACTURER PART NUMBER") "GRM155R71C104KA88D") (field (name "TOLERANCE") "10%"))
      (libsource (lib "Altium Content Vault") (part "236180d848d6139a670b325ea6854c9"))
    )
    (comp (ref "C91")
      (value "0.1uF")
      (footprint "FP-GRM15-MFG")
      (description "CAP CER 0.1UF 16V X7R 0402")
      (fields (field (name "MANUFACTURER PART NUMBER") "GRM155R71C104KA88D") (field (name "TOLERANCE") "10%"))
      (libsource (lib "Altium Content Vault") (part "236180d848d6139a670b325ea6854c9"))
    )
    (comp (ref "C92")
      (value "0.1uF")
      (footprint "FP-GRM15-MFG")
      (description "CAP CER 0.1UF 16V X7R 0402")
      (fields (field (name "MANUFACTURER PART NUMBER") "GRM155R71C104KA88D") (field (name "TOLERANCE") "10%"))
      (libsource (lib "Altium Content Vault") (part "236180d848d6139a670b325ea6854c9"))
    )
    (comp (ref "C93")
      (value "0.1uF")
      (footprint "FP-GRM15-MFG")
      (description "CAP CER 0.1UF 16V X7R 0402")
      (fields (field (name "MANUFACTURER PART NUMBER") "GRM155R71C104KA88D") (field (name "TOLERANCE") "10%"))
      (libsource (lib "Altium Content Vault") (part "236180d848d6139a670b325ea6854c9"))
    )
    (comp (ref "C94")
      (value "0.1uF")
      (footprint "FP-GRM15-MFG")
      (description "CAP CER 0.1UF 16V X7R 0402")
      (fields (field (name "MANUFACTURER PART NUMBER") "GRM155R71C104KA88D") (field (name "TOLERANCE") "10%"))
      (libsource (lib "Altium Content Vault") (part "236180d848d6139a670b325ea6854c9"))
    )
    (comp (ref "C95")
      (value "0.1uF")
      (footprint "FP-GRM15-MFG")
      (description "CAP CER 0.1UF 16V X7R 0402")
      (fields (field (name "MANUFACTURER PART NUMBER") "GRM155R71C104KA88D") (field (name "TOLERANCE") "10%"))
      (libsource (lib "Altium Content Vault") (part "236180d848d6139a670b325ea6854c9"))
    )
    (comp (ref "C96")
      (value "0.1uF")
      (footprint "FP-GRM15-MFG")
      (description "CAP CER 0.1UF 16V X7R 0402")
      (fields (field (name "MANUFACTURER PART NUMBER") "GRM155R71C104KA88D") (field (name "TOLERANCE") "10%"))
      (libsource (lib "Altium Content Vault") (part "236180d848d6139a670b325ea6854c9"))
    )
    (comp (ref "C97")
      (value "22uF")
      (footprint "FP-GRM21B-0_15-MFG")
      (description "Chip Multilayer Ceramic Capacitors for General Purpose, 0805, 22uF, X5R, 15%, 20%, 6.3V")
      (fields (field (name "VOLTAGE") "6.3V") (field (name "TOLERANCE") "20%"))
      (libsource (lib "Altium Content Vault") (part "b4654b650e69147ec39a6b967a45e02"))
    )
    (comp (ref "C98")
      (value "0.1uF")
      (footprint "FP-GRM15-MFG")
      (description "CAP CER 0.1UF 16V X7R 0402")
      (fields (field (name "MANUFACTURER PART NUMBER") "GRM155R71C104KA88D") (field (name "TOLERANCE") "10%"))
      (libsource (lib "Altium Content Vault") (part "236180d848d6139a670b325ea6854c9"))
    )
    (comp (ref "C99")
      (value "22uF")
      (footprint "FP-GRM21B-0_15-MFG")
      (description "Chip Multilayer Ceramic Capacitors for General Purpose, 0805, 22uF, X5R, 15%, 20%, 6.3V")
      (fields (field (name "VOLTAGE") "6.3V") (field (name "TOLERANCE") "20%"))
      (libsource (lib "Altium Content Vault") (part "b4654b650e69147ec39a6b967a45e02"))
    )
    (comp (ref "C100")
      (value "0.1uF")
      (footprint "FP-GRM15-MFG")
      (description "CAP CER 0.1UF 16V X7R 0402")
      (fields (field (name "MANUFACTURER PART NUMBER") "GRM155R71C104KA88D") (field (name "TOLERANCE") "10%"))
      (libsource (lib "Altium Content Vault") (part "236180d848d6139a670b325ea6854c9"))
    )
    (comp (ref "C101")
      (value "0.1uF")
      (footprint "FP-GRM15-MFG")
      (description "CAP CER 0.1UF 16V X7R 0402")
      (fields (field (name "MANUFACTURER PART NUMBER") "GRM155R71C104KA88D") (field (name "TOLERANCE") "10%"))
      (libsource (lib "Altium Content Vault") (part "236180d848d6139a670b325ea6854c9"))
    )
    (comp (ref "C102")
      (value "0.1uF")
      (footprint "FP-GRM15-MFG")
      (description "CAP CER 0.1UF 16V X7R 0402")
      (fields (field (name "MANUFACTURER PART NUMBER") "GRM155R71C104KA88D") (field (name "TOLERANCE") "10%"))
      (libsource (lib "Altium Content Vault") (part "236180d848d6139a670b325ea6854c9"))
    )
    (comp (ref "C103")
      (value "0.1uF")
      (footprint "FP-GRM15-MFG")
      (description "CAP CER 0.1UF 16V X7R 0402")
      (fields (field (name "MANUFACTURER PART NUMBER") "GRM155R71C104KA88D") (field (name "TOLERANCE") "10%"))
      (libsource (lib "Altium Content Vault") (part "236180d848d6139a670b325ea6854c9"))
    )
    (comp (ref "C104")
      (value "0.1uF")
      (footprint "FP-GRM15-MFG")
      (description "CAP CER 0.1UF 16V X7R 0402")
      (fields (field (name "MANUFACTURER PART NUMBER") "GRM155R71C104KA88D") (field (name "TOLERANCE") "10%"))
      (libsource (lib "Altium Content Vault") (part "236180d848d6139a670b325ea6854c9"))
    )
    (comp (ref "C105")
      (value "0.1uF")
      (footprint "FP-GRM15-MFG")
      (description "CAP CER 0.1UF 16V X7R 0402")
      (fields (field (name "MANUFACTURER PART NUMBER") "GRM155R71C104KA88D") (field (name "TOLERANCE") "10%"))
      (libsource (lib "Altium Content Vault") (part "236180d848d6139a670b325ea6854c9"))
    )
    (comp (ref "C106")
      (value "0.1uF")
      (footprint "FP-GRM15-MFG")
      (description "CAP CER 0.1UF 16V X7R 0402")
      (fields (field (name "MANUFACTURER PART NUMBER") "GRM155R71C104KA88D") (field (name "TOLERANCE") "10%"))
      (libsource (lib "Altium Content Vault") (part "236180d848d6139a670b325ea6854c9"))
    )
    (comp (ref "C107")
      (value "0.1uF")
      (footprint "FP-GRM15-MFG")
      (description "CAP CER 0.1UF 16V X7R 0402")
      (fields (field (name "MANUFACTURER PART NUMBER") "GRM155R71C104KA88D") (field (name "TOLERANCE") "10%"))
      (libsource (lib "Altium Content Vault") (part "236180d848d6139a670b325ea6854c9"))
    )
    (comp (ref "C108")
      (value "0.1uF")
      (footprint "FP-GRM15-MFG")
      (description "CAP CER 0.1UF 16V X7R 0402")
      (fields (field (name "MANUFACTURER PART NUMBER") "GRM155R71C104KA88D") (field (name "TOLERANCE") "10%"))
      (libsource (lib "Altium Content Vault") (part "236180d848d6139a670b325ea6854c9"))
    )
    (comp (ref "C109")
      (value "0.1uF")
      (footprint "FP-GRM15-MFG")
      (description "CAP CER 0.1UF 16V X7R 0402")
      (fields (field (name "MANUFACTURER PART NUMBER") "GRM155R71C104KA88D") (field (name "TOLERANCE") "10%"))
      (libsource (lib "Altium Content Vault") (part "236180d848d6139a670b325ea6854c9"))
    )
    (comp (ref "C110")
      (value "0.1uF")
      (footprint "FP-GRM15-MFG")
      (description "CAP CER 0.1UF 16V X7R 0402")
      (fields (field (name "MANUFACTURER PART NUMBER") "GRM155R71C104KA88D") (field (name "TOLERANCE") "10%"))
      (libsource (lib "Altium Content Vault") (part "236180d848d6139a670b325ea6854c9"))
    )
    (comp (ref "C111")
      (value "0.1uF")
      (footprint "FP-GRM15-MFG")
      (description "CAP CER 0.1UF 16V X7R 0402")
      (fields (field (name "MANUFACTURER PART NUMBER") "GRM155R71C104KA88D") (field (name "TOLERANCE") "10%"))
      (libsource (lib "Altium Content Vault") (part "236180d848d6139a670b325ea6854c9"))
    )
    (comp (ref "C112")
      (value "0.1uF")
      (footprint "FP-GRM15-MFG")
      (description "CAP CER 0.1UF 16V X7R 0402")
      (fields (field (name "MANUFACTURER PART NUMBER") "GRM155R71C104KA88D") (field (name "TOLERANCE") "10%"))
      (libsource (lib "Altium Content Vault") (part "236180d848d6139a670b325ea6854c9"))
    )
    (comp (ref "C113")
      (value "0.1uF")
      (footprint "FP-GRM15-MFG")
      (description "CAP CER 0.1UF 16V X7R 0402")
      (fields (field (name "MANUFACTURER PART NUMBER") "GRM155R71C104KA88D") (field (name "TOLERANCE") "10%"))
      (libsource (lib "Altium Content Vault") (part "236180d848d6139a670b325ea6854c9"))
    )
    (comp (ref "C114")
      (value "10uF")
      (footprint "FP-C0805C-DG-MFG")
      (description "CAP CER 10UF 10V X5R 0805")
      (fields (field (name "TOLERANCE") "10%") (field (name "MANUFACTURER PART NUMBER") "C0805C106K8PACTU"))
      (libsource (lib "Altium Content Vault") (part "11868f565c42a9108669ba33697ecf6"))
    )
    (comp (ref "C115")
      (value "0.1uF")
      (footprint "FP-GRM15-MFG")
      (description "CAP CER 0.1UF 16V X7R 0402")
      (fields (field (name "MANUFACTURER PART NUMBER") "GRM155R71C104KA88D") (field (name "TOLERANCE") "10%"))
      (libsource (lib "Altium Content Vault") (part "236180d848d6139a670b325ea6854c9"))
    )
    (comp (ref "C116")
      (value "22uF")
      (footprint "FP-GRM21B-0_15-MFG")
      (description "Chip Multilayer Ceramic Capacitors for General Purpose, 0805, 22uF, X5R, 15%, 20%, 6.3V")
      (fields (field (name "VOLTAGE") "6.3V") (field (name "TOLERANCE") "20%"))
      (libsource (lib "Altium Content Vault") (part "b4654b650e69147ec39a6b967a45e02"))
    )
    (comp (ref "C117")
      (value "1500pF")
      (footprint "FP-C0402-BB-MFG")
      (description "CAP CER 1500PF 50V X7R 0402")
      (fields
        (field (name "OCTOPART") "https://octopart.com/c0402c152k5ractu-kemet-125298")
        (field (name "TOLERANCE") "0.1")
      )
      (libsource (lib "Altium Content Vault") (part "b4654b650e69147ec39a6b967a45e02"))
    )
    (comp (ref "C118")
      (value "0.1uF")
      (footprint "FP-GRM15-MFG")
      (description "CAP CER 0.1UF 16V X7R 0402")
      (fields (field (name "MANUFACTURER PART NUMBER") "GRM155R71C104KA88D") (field (name "TOLERANCE") "10%"))
      (libsource (lib "Altium Content Vault") (part "236180d848d6139a670b325ea6854c9"))
    )
    (comp (ref "C119")
      (value "0.1uF")
      (footprint "FP-GRM15-MFG")
      (description "CAP CER 0.1UF 16V X7R 0402")
      (fields (field (name "MANUFACTURER PART NUMBER") "GRM155R71C104KA88D") (field (name "TOLERANCE") "10%"))
      (libsource (lib "Altium Content Vault") (part "236180d848d6139a670b325ea6854c9"))
    )
    (comp (ref "C120")
      (value "0.1uF")
      (footprint "FP-GRM15-MFG")
      (description "CAP CER 0.1UF 16V X7R 0402")
      (fields (field (name "MANUFACTURER PART NUMBER") "GRM155R71C104KA88D") (field (name "TOLERANCE") "10%"))
      (libsource (lib "Altium Content Vault") (part "236180d848d6139a670b325ea6854c9"))
    )
    (comp (ref "C121")
      (value "0.1uF")
      (footprint "FP-GRM15-MFG")
      (description "CAP CER 0.1UF 16V X7R 0402")
      (fields (field (name "MANUFACTURER PART NUMBER") "GRM155R71C104KA88D") (field (name "TOLERANCE") "10%"))
      (libsource (lib "Altium Content Vault") (part "236180d848d6139a670b325ea6854c9"))
    )
    (comp (ref "C122")
      (value "22uF")
      (footprint "FP-GRM21B-0_15-MFG")
      (description "Chip Multilayer Ceramic Capacitors for General Purpose, 0805, 22uF, X5R, 15%, 20%, 6.3V")
      (fields (field (name "VOLTAGE") "6.3V") (field (name "TOLERANCE") "20%"))
      (libsource (lib "Altium Content Vault") (part "b4654b650e69147ec39a6b967a45e02"))
    )
    (comp (ref "C123")
      (value "0.1uF")
      (footprint "FP-GRM15-MFG")
      (description "CAP CER 0.1UF 16V X7R 0402")
      (fields (field (name "MANUFACTURER PART NUMBER") "GRM155R71C104KA88D") (field (name "TOLERANCE") "10%"))
      (libsource (lib "Altium Content Vault") (part "236180d848d6139a670b325ea6854c9"))
    )
    (comp (ref "C124")
      (value "2.2uF")
      (footprint "CAPC1005X55X30NL05T10")
      (fields (field (name "MANUFACTURER") "Kemet") (field (name "PART NUMBER") "C0402C225M9PACTU"))
      (libsource (lib "Altium Content Vault") (part "CAP"))
    )
    (comp (ref "C125")
      (value "2.2uF")
      (footprint "CAPC1005X55X30NL05T10")
      (fields (field (name "MANUFACTURER") "Kemet") (field (name "PART NUMBER") "C0402C225M9PACTU"))
      (libsource (lib "Altium Content Vault") (part "CAP"))
    )
    (comp (ref "C126")
      (value "3000pF")
      (footprint "FP-GRM155-0_05-IPC_B")
      (description "Chip Multilayer Ceramic Capacitors for General Purpose, 0402, 3000pF, U2J, -750ppm/°C, 5%, 10V")
      (fields (field (name "TOLERANCE") "5%"))
      (libsource (lib "Altium Content Vault") (part "02cd4be3c70576c341d710602a673aa"))
    )
    (comp (ref "C127")
      (value "1500pF")
      (footprint "FP-C0402-BB-MFG")
      (description "CAP CER 1500PF 50V X7R 0402")
      (fields
        (field (name "OCTOPART") "https://octopart.com/c0402c152k5ractu-kemet-125298")
        (field (name "TOLERANCE") "0.1")
      )
      (libsource (lib "Altium Content Vault") (part "b4654b650e69147ec39a6b967a45e02"))
    )
    (comp (ref "C128")
      (value "0.1uF")
      (footprint "FP-GRM15-MFG")
      (description "CAP CER 0.1UF 16V X7R 0402")
      (fields (field (name "MANUFACTURER PART NUMBER") "GRM155R71C104KA88D") (field (name "TOLERANCE") "10%"))
      (libsource (lib "Altium Content Vault") (part "236180d848d6139a670b325ea6854c9"))
    )
    (comp (ref "C129")
      (value "0.1uF")
      (footprint "FP-GRM15-MFG")
      (description "CAP CER 0.1UF 16V X7R 0402")
      (fields (field (name "MANUFACTURER PART NUMBER") "GRM155R71C104KA88D") (field (name "TOLERANCE") "10%"))
      (libsource (lib "Altium Content Vault") (part "236180d848d6139a670b325ea6854c9"))
    )
    (comp (ref "C130")
      (value "0.1uF")
      (footprint "FP-GRM15-MFG")
      (description "CAP CER 0.1UF 16V X7R 0402")
      (fields (field (name "MANUFACTURER PART NUMBER") "GRM155R71C104KA88D") (field (name "TOLERANCE") "10%"))
      (libsource (lib "Altium Content Vault") (part "236180d848d6139a670b325ea6854c9"))
    )
    (comp (ref "C131")
      (value "0.1uF")
      (footprint "FP-GRM15-MFG")
      (description "CAP CER 0.1UF 16V X7R 0402")
      (fields (field (name "MANUFACTURER PART NUMBER") "GRM155R71C104KA88D") (field (name "TOLERANCE") "10%"))
      (libsource (lib "Altium Content Vault") (part "236180d848d6139a670b325ea6854c9"))
    )
    (comp (ref "C132")
      (value "0.1uF")
      (footprint "FP-GRM15-MFG")
      (description "CAP CER 0.1UF 16V X7R 0402")
      (fields (field (name "MANUFACTURER PART NUMBER") "GRM155R71C104KA88D") (field (name "TOLERANCE") "10%"))
      (libsource (lib "Altium Content Vault") (part "236180d848d6139a670b325ea6854c9"))
    )
    (comp (ref "C133")
      (value "0.1uF")
      (footprint "FP-GRM15-MFG")
      (description "CAP CER 0.1UF 16V X7R 0402")
      (fields (field (name "MANUFACTURER PART NUMBER") "GRM155R71C104KA88D") (field (name "TOLERANCE") "10%"))
      (libsource (lib "Altium Content Vault") (part "236180d848d6139a670b325ea6854c9"))
    )
    (comp (ref "C134")
      (value "0.1uF")
      (footprint "FP-GRM15-MFG")
      (description "CAP CER 0.1UF 16V X7R 0402")
      (fields (field (name "MANUFACTURER PART NUMBER") "GRM155R71C104KA88D") (field (name "TOLERANCE") "10%"))
      (libsource (lib "Altium Content Vault") (part "236180d848d6139a670b325ea6854c9"))
    )
    (comp (ref "C135")
      (value "0.1uF")
      (footprint "FP-GRM15-MFG")
      (description "CAP CER 0.1UF 16V X7R 0402")
      (fields (field (name "MANUFACTURER PART NUMBER") "GRM155R71C104KA88D") (field (name "TOLERANCE") "10%"))
      (libsource (lib "Altium Content Vault") (part "236180d848d6139a670b325ea6854c9"))
    )
    (comp (ref "C136")
      (value "3000pF")
      (footprint "FP-GRM155-0_05-IPC_B")
      (description "Chip Multilayer Ceramic Capacitors for General Purpose, 0402, 3000pF, U2J, -750ppm/°C, 5%, 10V")
      (fields (field (name "TOLERANCE") "5%"))
      (libsource (lib "Altium Content Vault") (part "02cd4be3c70576c341d710602a673aa"))
    )
    (comp (ref "C137")
      (value "1500pF")
      (footprint "FP-C0402-BB-MFG")
      (description "CAP CER 1500PF 50V X7R 0402")
      (fields
        (field (name "OCTOPART") "https://octopart.com/c0402c152k5ractu-kemet-125298")
        (field (name "TOLERANCE") "0.1")
      )
      (libsource (lib "Altium Content Vault") (part "b4654b650e69147ec39a6b967a45e02"))
    )
    (comp (ref "C138")
      (value "22uF")
      (footprint "FP-GRM21B-0_15-MFG")
      (description "Chip Multilayer Ceramic Capacitors for General Purpose, 0805, 22uF, X5R, 15%, 20%, 6.3V")
      (fields (field (name "VOLTAGE") "6.3V") (field (name "TOLERANCE") "20%"))
      (libsource (lib "Altium Content Vault") (part "b4654b650e69147ec39a6b967a45e02"))
    )
    (comp (ref "C139")
      (value "22uF")
      (footprint "FP-GRM21B-0_15-MFG")
      (description "Chip Multilayer Ceramic Capacitors for General Purpose, 0805, 22uF, X5R, 15%, 20%, 6.3V")
      (fields (field (name "VOLTAGE") "6.3V") (field (name "TOLERANCE") "20%"))
      (libsource (lib "Altium Content Vault") (part "b4654b650e69147ec39a6b967a45e02"))
    )
    (comp (ref "C140")
      (value "22uF")
      (footprint "FP-GRM21B-0_15-MFG")
      (description "Chip Multilayer Ceramic Capacitors for General Purpose, 0805, 22uF, X5R, 15%, 20%, 6.3V")
      (fields (field (name "VOLTAGE") "6.3V") (field (name "TOLERANCE") "20%"))
      (libsource (lib "Altium Content Vault") (part "b4654b650e69147ec39a6b967a45e02"))
    )
    (comp (ref "C141")
      (value "2.2uF")
      (footprint "CAPC1005X55X30NL05T10")
      (fields (field (name "MANUFACTURER") "Kemet") (field (name "PART NUMBER") "C0402C225M9PACTU"))
      (libsource (lib "Altium Content Vault") (part "CAP"))
    )
    (comp (ref "C142")
      (value "2.2uF")
      (footprint "CAPC1005X55X30NL05T10")
      (fields (field (name "MANUFACTURER") "Kemet") (field (name "PART NUMBER") "C0402C225M9PACTU"))
      (libsource (lib "Altium Content Vault") (part "CAP"))
    )
    (comp (ref "C143")
      (value "1uF")
      (footprint "CAPC1005X60X30LL05T10")
      (fields (field (name "PART NUMBER") "C0402C105K8PAC7867") (field (name "MANUFACTURER") "Kemet"))
      (libsource (lib "Altium Content Vault") (part "CAP"))
    )
    (comp (ref "C144")
      (value "10uF")
      (footprint "FP-C0805C-DG-MFG")
      (description "CAP CER 10UF 10V X5R 0805")
      (fields (field (name "TOLERANCE") "10%") (field (name "MANUFACTURER PART NUMBER") "C0805C106K8PACTU"))
      (libsource (lib "Altium Content Vault") (part "11868f565c42a9108669ba33697ecf6"))
    )
    (comp (ref "C145")
      (value "3000pF")
      (footprint "FP-GRM155-0_05-IPC_B")
      (description "Chip Multilayer Ceramic Capacitors for General Purpose, 0402, 3000pF, U2J, -750ppm/°C, 5%, 10V")
      (fields (field (name "TOLERANCE") "5%"))
      (libsource (lib "Altium Content Vault") (part "02cd4be3c70576c341d710602a673aa"))
    )
    (comp (ref "C146")
      (value "4.7uF")
      (footprint "FP-GRM188-0_2-IPC_C")
      (description "Chip Multilayer Ceramic Capacitors for General Purpose, 0603, 4.7uF, X5R, 15%, 10%, 35V")
      (fields (field (name "VOLTAGE") "35V") (field (name "TOLERANCE") "10%"))
      (libsource (lib "Altium Content Vault") (part "11868f565c42a9108669ba33697ecf6"))
    )
    (comp (ref "C147")
      (value "0.47uF")
      (footprint "FP-GRM188-0_1-e0_2_0_5-IPC_B")
      (description "Chip Multilayer Ceramic Capacitors for General Purpose, 0603, 0.47uF, X7R, 15%, 10%, 16V")
      (fields (field (name "VOLTAGE") "16V") (field (name "TOLERANCE") "10%"))
      (libsource (lib "Altium Content Vault") (part "11868f565c42a9108669ba33697ecf6"))
    )
    (comp (ref "C148")
      (value "1uF")
      (footprint "CAPC1005X60X30LL05T10")
      (fields (field (name "PART NUMBER") "C0402C105K8PAC7867") (field (name "MANUFACTURER") "Kemet"))
      (libsource (lib "Altium Content Vault") (part "CAP"))
    )
    (comp (ref "C149")
      (value "10uF")
      (footprint "FP-C0805C-DG-MFG")
      (description "CAP CER 10UF 10V X5R 0805")
      (fields (field (name "TOLERANCE") "10%") (field (name "MANUFACTURER PART NUMBER") "C0805C106K8PACTU"))
      (libsource (lib "Altium Content Vault") (part "11868f565c42a9108669ba33697ecf6"))
    )
    (comp (ref "C150")
      (value "3000pF")
      (footprint "FP-GRM155-0_05-IPC_B")
      (description "Chip Multilayer Ceramic Capacitors for General Purpose, 0402, 3000pF, U2J, -750ppm/°C, 5%, 10V")
      (fields (field (name "TOLERANCE") "5%"))
      (libsource (lib "Altium Content Vault") (part "02cd4be3c70576c341d710602a673aa"))
    )
    (comp (ref "C151")
      (value "4.7uF")
      (footprint "FP-GRM188-0_2-IPC_C")
      (description "Chip Multilayer Ceramic Capacitors for General Purpose, 0603, 4.7uF, X5R, 15%, 10%, 35V")
      (fields (field (name "VOLTAGE") "35V") (field (name "TOLERANCE") "10%"))
      (libsource (lib "Altium Content Vault") (part "11868f565c42a9108669ba33697ecf6"))
    )
    (comp (ref "C152")
      (value "0.47uF")
      (footprint "FP-GRM188-0_1-e0_2_0_5-IPC_B")
      (description "Chip Multilayer Ceramic Capacitors for General Purpose, 0603, 0.47uF, X7R, 15%, 10%, 16V")
      (fields (field (name "VOLTAGE") "16V") (field (name "TOLERANCE") "10%"))
      (libsource (lib "Altium Content Vault") (part "11868f565c42a9108669ba33697ecf6"))
    )
    (comp (ref "C153")
      (value "1uF")
      (footprint "CAPC1005X60X30LL05T10")
      (fields (field (name "PART NUMBER") "C0402C105K8PAC7867") (field (name "MANUFACTURER") "Kemet"))
      (libsource (lib "Altium Content Vault") (part "CAP"))
    )
    (comp (ref "C154")
      (value "10uF")
      (footprint "FP-C0805C-DG-MFG")
      (description "CAP CER 10UF 10V X5R 0805")
      (fields (field (name "TOLERANCE") "10%") (field (name "MANUFACTURER PART NUMBER") "C0805C106K8PACTU"))
      (libsource (lib "Altium Content Vault") (part "11868f565c42a9108669ba33697ecf6"))
    )
    (comp (ref "C155")
      (value "1uF")
      (footprint "CAPC1005X60X30LL05T10")
      (fields (field (name "PART NUMBER") "C0402C105K8PAC7867") (field (name "MANUFACTURER") "Kemet"))
      (libsource (lib "Altium Content Vault") (part "CAP"))
    )
    (comp (ref "C156")
      (value "10uF")
      (footprint "FP-C0805C-DG-MFG")
      (description "CAP CER 10UF 10V X5R 0805")
      (fields (field (name "TOLERANCE") "10%") (field (name "MANUFACTURER PART NUMBER") "C0805C106K8PACTU"))
      (libsource (lib "Altium Content Vault") (part "11868f565c42a9108669ba33697ecf6"))
    )
    (comp (ref "IC1")
      (value "LS1043ASN8QQB")
      (footprint "SamacSys:BGA780C80P28X28_2300X2300X261")
      (description "Integrated Circuit")
      (fields (field (name "MOUSER PART NUMBER") "771-LS1043ASN8QQB"))
      (libsource (lib "SamacSys") (part "LS1043ASN8QQB"))
    )
    (comp (ref "L1")
      (value "220nH")
      (footprint "FP-MPLCG0530-MFG")
      (description "FIXED IND 220NH 14.1A 3.7 MOHM")
      (fields
        (field (name "OCTOPART") "https://octopart.com/mplcg0530lr22-kemet-30531716")
        (field (name "MANUFACTURER") "KEMET")
      )
      (libsource (lib "Altium Content Vault") (part "725321dda6339637d4d059423bc1c3c"))
    )
    (comp (ref "L2")
      (value "220nH")
      (footprint "FP-MPLCG0530-MFG")
      (description "FIXED IND 220NH 14.1A 3.7 MOHM")
      (fields
        (field (name "OCTOPART") "https://octopart.com/mplcg0530lr22-kemet-30531716")
        (field (name "MANUFACTURER") "KEMET")
      )
      (libsource (lib "Altium Content Vault") (part "725321dda6339637d4d059423bc1c3c"))
    )
    (comp (ref "L3")
      (value "220nH")
      (footprint "FP-MPLCG0530-MFG")
      (description "FIXED IND 220NH 14.1A 3.7 MOHM")
      (fields
        (field (name "OCTOPART") "https://octopart.com/mplcg0530lr22-kemet-30531716")
        (field (name "MANUFACTURER") "KEMET")
      )
      (libsource (lib "Altium Content Vault") (part "725321dda6339637d4d059423bc1c3c"))
    )
    (comp (ref "L4")
      (value "220nH")
      (footprint "FP-MPLCG0530-MFG")
      (description "FIXED IND 220NH 14.1A 3.7 MOHM")
      (fields
        (field (name "OCTOPART") "https://octopart.com/mplcg0530lr22-kemet-30531716")
        (field (name "MANUFACTURER") "KEMET")
      )
      (libsource (lib "Altium Content Vault") (part "725321dda6339637d4d059423bc1c3c"))
    )
    (comp (ref "L5")
      (value "220nH")
      (footprint "FP-MPLCG0530-MFG")
      (description "FIXED IND 220NH 14.1A 3.7 MOHM")
      (fields
        (field (name "OCTOPART") "https://octopart.com/mplcg0530lr22-kemet-30531716")
        (field (name "MANUFACTURER") "KEMET")
      )
      (libsource (lib "Altium Content Vault") (part "725321dda6339637d4d059423bc1c3c"))
    )
    (comp (ref "L6")
      (value "220nH")
      (footprint "FP-MPLCG0530-MFG")
      (description "FIXED IND 220NH 14.1A 3.7 MOHM")
      (fields
        (field (name "OCTOPART") "https://octopart.com/mplcg0530lr22-kemet-30531716")
        (field (name "MANUFACTURER") "KEMET")
      )
      (libsource (lib "Altium Content Vault") (part "725321dda6339637d4d059423bc1c3c"))
    )
    (comp (ref "L7")
      (value "220nH")
      (footprint "FP-MPLCG0530-MFG")
      (description "FIXED IND 220NH 14.1A 3.7 MOHM")
      (fields
        (field (name "OCTOPART") "https://octopart.com/mplcg0530lr22-kemet-30531716")
        (field (name "MANUFACTURER") "KEMET")
      )
      (libsource (lib "Altium Content Vault") (part "725321dda6339637d4d059423bc1c3c"))
    )
    (comp (ref "L8")
      (value "220nH")
      (footprint "FP-MPLCG0530-MFG")
      (description "FIXED IND 220NH 14.1A 3.7 MOHM")
      (fields
        (field (name "OCTOPART") "https://octopart.com/mplcg0530lr22-kemet-30531716")
        (field (name "MANUFACTURER") "KEMET")
      )
      (libsource (lib "Altium Content Vault") (part "725321dda6339637d4d059423bc1c3c"))
    )
    (comp (ref "L9")
      (value "220nH")
      (footprint "FP-MPLCG0530-MFG")
      (description "FIXED IND 220NH 14.1A 3.7 MOHM")
      (fields
        (field (name "OCTOPART") "https://octopart.com/mplcg0530lr22-kemet-30531716")
        (field (name "MANUFACTURER") "KEMET")
      )
      (libsource (lib "Altium Content Vault") (part "725321dda6339637d4d059423bc1c3c"))
    )
    (comp (ref "L10")
      (value "220nH")
      (footprint "FP-MPLCG0530-MFG")
      (description "FIXED IND 220NH 14.1A 3.7 MOHM")
      (fields
        (field (name "OCTOPART") "https://octopart.com/mplcg0530lr22-kemet-30531716")
        (field (name "MANUFACTURER") "KEMET")
      )
      (libsource (lib "Altium Content Vault") (part "725321dda6339637d4d059423bc1c3c"))
    )
    (comp (ref "L11")
      (value "220nH")
      (footprint "FP-MPLCG0530-MFG")
      (description "FIXED IND 220NH 14.1A 3.7 MOHM")
      (fields
        (field (name "OCTOPART") "https://octopart.com/mplcg0530lr22-kemet-30531716")
        (field (name "MANUFACTURER") "KEMET")
      )
      (libsource (lib "Altium Content Vault") (part "725321dda6339637d4d059423bc1c3c"))
    )
    (comp (ref "P1")
      (value "5-146280-2")
      (footprint "TECO-5-146280-2_V")
      (fields (field (name "MANUFACTURER") "TE Connectivity"))
      (libsource (lib "Altium Content Vault") (part "CN-1P-M-R2"))
    )
    (comp (ref "P2")
      (value "5-146280-2")
      (footprint "TECO-5-146280-2_V")
      (fields (field (name "MANUFACTURER") "TE Connectivity"))
      (libsource (lib "") (part "CN-1P-M-R2_1"))
    )
    (comp (ref "P3")
      (value "5-146280-2")
      (footprint "TECO-5-146280-2_V")
      (fields (field (name "MANUFACTURER") "TE Connectivity"))
      (libsource (lib "") (part "CN-1P-M-R2_1"))
    )
    (comp (ref "P4")
      (value "5-146280-2")
      (footprint "TECO-5-146280-2_V")
      (fields (field (name "MANUFACTURER") "TE Connectivity"))
      (libsource (lib "") (part "CN-1P-M-R2_1"))
    )
    (comp (ref "R1")
      (value "10")
      (footprint "RESC1005X40X25NL05T05")
      (fields (field (name "PART NUMBER") "CRCW040210R0FKED") (field (name "MANUFACTURER") "Vishay Dale"))
      (libsource (lib "Altium Content Vault") (part "RES"))
    )
    (comp (ref "R2")
      (value "10")
      (footprint "RESC1005X40X25NL05T05")
      (fields (field (name "PART NUMBER") "CRCW040210R0FKED") (field (name "MANUFACTURER") "Vishay Dale"))
      (libsource (lib "Altium Content Vault") (part "RES"))
    )
    (comp (ref "R3")
      (value "330")
      (footprint "FP-CRCW0402-e3-IPC_B")
      (description "RES Thick Film, 330Ω, 1%, 0.063W, 100ppm/°C, 0402")
      (fields (field (name "TOLERANCE") "1%"))
      (libsource (lib "Altium Content Vault") (part "1029c3af85768c4190bb7ad29bc67b5"))
    )
    (comp (ref "R4")
      (value "330")
      (footprint "FP-CRCW0402-e3-MFG")
      (description "RES Thick Film, 330Ω, 1%, 0.063W, 100ppm/°C, 0402")
      (fields (field (name "TOLERANCE") "1%"))
      (libsource (lib "Altium Content Vault") (part "1029c3af85768c4190bb7ad29bc67b5"))
    )
    (comp (ref "R5")
      (value "330")
      (footprint "FP-CRCW0402-e3-MFG")
      (description "RES Thick Film, 330Ω, 1%, 0.063W, 100ppm/°C, 0402")
      (fields (field (name "TOLERANCE") "1%"))
      (libsource (lib "Altium Content Vault") (part "1029c3af85768c4190bb7ad29bc67b5"))
    )
    (comp (ref "R6")
      (value "330")
      (footprint "FP-CRCW0402-e3-MFG")
      (description "RES Thick Film, 330Ω, 1%, 0.063W, 100ppm/°C, 0402")
      (fields (field (name "TOLERANCE") "1%"))
      (libsource (lib "Altium Content Vault") (part "1029c3af85768c4190bb7ad29bc67b5"))
    )
    (comp (ref "R7")
      (value "330")
      (footprint "FP-CRCW0402-e3-MFG")
      (description "RES Thick Film, 330Ω, 1%, 0.063W, 100ppm/°C, 0402")
      (fields (field (name "TOLERANCE") "1%"))
      (libsource (lib "Altium Content Vault") (part "1029c3af85768c4190bb7ad29bc67b5"))
    )
    (comp (ref "R8")
      (value "5.1")
      (footprint "RESC1005X40X25LL05T05")
      (fields (field (name "PART NUMBER") "CRCW04025R10FKED") (field (name "MANUFACTURER") "Vishay Dale"))
      (libsource (lib "Altium Content Vault") (part "RES"))
    )
    (comp (ref "R9")
      (value "5.1")
      (footprint "RESC1005X40X25LL05T05")
      (fields (field (name "PART NUMBER") "CRCW04025R10FKED") (field (name "MANUFACTURER") "Vishay Dale"))
      (libsource (lib "Altium Content Vault") (part "RES"))
    )
    (comp (ref "R10")
      (value "0.33")
      (footprint "RESC2013X50X40LL20T20")
      (fields (field (name "MANUFACTURER") "Susumu") (field (name "PART NUMBER") "RP2012T-R33-F"))
      (libsource (lib "Altium Content Vault") (part "RES"))
    )
    (comp (ref "R11")
      (value "0.33")
      (footprint "RESC2013X50X40LL20T20")
      (fields (field (name "MANUFACTURER") "Susumu") (field (name "PART NUMBER") "RP2012T-R33-F"))
      (libsource (lib "Altium Content Vault") (part "RES"))
    )
    (comp (ref "R12")
      (value "5.1")
      (footprint "RESC1005X40X25LL05T05")
      (fields (field (name "PART NUMBER") "CRCW04025R10FKED") (field (name "MANUFACTURER") "Vishay Dale"))
      (libsource (lib "Altium Content Vault") (part "RES"))
    )
    (comp (ref "R13")
      (value "5.1")
      (footprint "RESC1005X40X25LL05T05")
      (fields (field (name "PART NUMBER") "CRCW04025R10FKED") (field (name "MANUFACTURER") "Vishay Dale"))
      (libsource (lib "Altium Content Vault") (part "RES"))
    )
  )
  (nets
    (net (code "1") (name "+1V8") (class "Default")
      (node (ref "C113") (pin "2") (pinfunction "2_2") (pintype "passive"))
      (node (ref "C114") (pin "1") (pinfunction "1_1") (pintype "passive"))
      (node (ref "C121") (pin "2") (pinfunction "2_2") (pintype "passive"))
      (node (ref "C122") (pin "1") (pinfunction "1_1") (pintype "passive"))
      (node (ref "C65") (pin "2") (pinfunction "2_2") (pintype "passive"))
      (node (ref "C66") (pin "2") (pinfunction "2_2") (pintype "passive"))
      (node (ref "C67") (pin "2") (pinfunction "2_2") (pintype "passive"))
      (node (ref "C68") (pin "2") (pinfunction "2_2") (pintype "passive"))
      (node (ref "C69") (pin "2") (pinfunction "2_2") (pintype "passive"))
      (node (ref "C70") (pin "2") (pinfunction "2_2") (pintype "passive"))
      (node (ref "C71") (pin "2") (pinfunction "2_2") (pintype "passive"))
      (node (ref "C72") (pin "1") (pinfunction "1_1") (pintype "passive"))
      (node (ref "C73") (pin "1") (pinfunction "1_1") (pintype "passive"))
      (node (ref "IC1") (pin "J12") (pinfunction "OVDD1_J12") (pintype "passive"))
      (node (ref "IC1") (pin "J13") (pinfunction "OVDD2_J13") (pintype "passive"))
      (node (ref "IC1") (pin "J14") (pinfunction "OVDD3_J14") (pintype "passive"))
      (node (ref "IC1") (pin "J15") (pinfunction "OVDD4_J15") (pintype "passive"))
      (node (ref "IC1") (pin "J16") (pinfunction "OVDD5_J16") (pintype "passive"))
      (node (ref "IC1") (pin "J17") (pinfunction "OVDD6_J17") (pintype "passive"))
      (node (ref "IC1") (pin "N7") (pinfunction "OVDD7_N7") (pintype "passive"))
      (node (ref "IC1") (pin "T6") (pinfunction "TH_VDD_T6") (pintype "passive"))
      (node (ref "L5") (pin "2") (pinfunction "2_2") (pintype "passive"))
      (node (ref "P2") (pin "1") (pinfunction "1_1") (pintype "passive"))
      (node (ref "P3") (pin "2") (pinfunction "2_2") (pintype "passive"))
      (node (ref "R12") (pin "1") (pinfunction "1_1") (pintype "passive"))
      (node (ref "R13") (pin "1") (pinfunction "1_1") (pintype "passive"))
      (node (ref "R4") (pin "2") (pinfunction "2_2") (pintype "passive"))
      (node (ref "R8") (pin "1") (pinfunction "1_1") (pintype "passive"))
      (node (ref "R9") (pin "1") (pinfunction "1_1") (pintype "passive"))
    )
    (net (code "2") (name "+2V5") (class "Default")
      (node (ref "L4") (pin "2") (pinfunction "2_2") (pintype "passive"))
      (node (ref "L7") (pin "1") (pinfunction "1_1") (pintype "passive"))
    )
    (net (code "3") (name "+3V3") (class "Default")
      (node (ref "L3") (pin "2") (pinfunction "2_2") (pintype "passive"))
      (node (ref "L6") (pin "2") (pinfunction "2_2") (pintype "passive"))
    )
    (net (code "4") (name "+CPU_VDD") (class "Default")
      (node (ref "C10") (pin "1") (pinfunction "1_1") (pintype "passive"))
      (node (ref "C11") (pin "1") (pinfunction "1_1") (pintype "passive"))
      (node (ref "C12") (pin "1") (pinfunction "1_1") (pintype "passive"))
      (node (ref "C13") (pin "1") (pinfunction "1_1") (pintype "passive"))
      (node (ref "C14") (pin "2") (pinfunction "2_2") (pintype "passive"))
      (node (ref "C15") (pin "2") (pinfunction "2_2") (pintype "passive"))
      (node (ref "C16") (pin "2") (pinfunction "2_2") (pintype "passive"))
      (node (ref "C17") (pin "2") (pinfunction "2_2") (pintype "passive"))
      (node (ref "C18") (pin "2") (pinfunction "2_2") (pintype "passive"))
      (node (ref "C19") (pin "2") (pinfunction "2_2") (pintype "passive"))
      (node (ref "C20") (pin "2") (pinfunction "2_2") (pintype "passive"))
      (node (ref "C21") (pin "2") (pinfunction "2_2") (pintype "passive"))
      (node (ref "C22") (pin "2") (pinfunction "2_2") (pintype "passive"))
      (node (ref "C23") (pin "2") (pinfunction "2_2") (pintype "passive"))
      (node (ref "C24") (pin "1") (pinfunction "1_1") (pintype "passive"))
      (node (ref "C25") (pin "1") (pinfunction "1_1") (pintype "passive"))
      (node (ref "C26") (pin "1") (pinfunction "1_1") (pintype "passive"))
      (node (ref "C31") (pin "2") (pinfunction "2_2") (pintype "passive"))
      (node (ref "C32") (pin "2") (pinfunction "2_2") (pintype "passive"))
      (node (ref "C33") (pin "2") (pinfunction "2_2") (pintype "passive"))
      (node (ref "C34") (pin "2") (pinfunction "2_2") (pintype "passive"))
      (node (ref "C35") (pin "2") (pinfunction "2_2") (pintype "passive"))
      (node (ref "C36") (pin "2") (pinfunction "2_2") (pintype "passive"))
      (node (ref "C37") (pin "2") (pinfunction "2_2") (pintype "passive"))
      (node (ref "C38") (pin "2") (pinfunction "2_2") (pintype "passive"))
      (node (ref "C39") (pin "2") (pinfunction "2_2") (pintype "passive"))
      (node (ref "C40") (pin "2") (pinfunction "2_2") (pintype "passive"))
      (node (ref "C41") (pin "1") (pinfunction "1_1") (pintype "passive"))
      (node (ref "C42") (pin "1") (pinfunction "1_1") (pintype "passive"))
      (node (ref "C43") (pin "1") (pinfunction "1_1") (pintype "passive"))
      (node (ref "C48") (pin "2") (pinfunction "2_2") (pintype "passive"))
      (node (ref "C49") (pin "2") (pinfunction "2_2") (pintype "passive"))
      (node (ref "C5") (pin "1") (pinfunction "1_1") (pintype "passive"))
      (node (ref "C50") (pin "2") (pinfunction "2_2") (pintype "passive"))
      (node (ref "C51") (pin "2") (pinfunction "2_2") (pintype "passive"))
      (node (ref "C52") (pin "2") (pinfunction "2_2") (pintype "passive"))
      (node (ref "C53") (pin "2") (pinfunction "2_2") (pintype "passive"))
      (node (ref "C54") (pin "2") (pinfunction "2_2") (pintype "passive"))
      (node (ref "C55") (pin "2") (pinfunction "2_2") (pintype "passive"))
      (node (ref "C56") (pin "2") (pinfunction "2_2") (pintype "passive"))
      (node (ref "C57") (pin "2") (pinfunction "2_2") (pintype "passive"))
      (node (ref "C58") (pin "1") (pinfunction "1_1") (pintype "passive"))
      (node (ref "C59") (pin "1") (pinfunction "1_1") (pintype "passive"))
      (node (ref "C6") (pin "1") (pinfunction "1_1") (pintype "passive"))
      (node (ref "C60") (pin "1") (pinfunction "1_1") (pintype "passive"))
      (node (ref "C7") (pin "1") (pinfunction "1_1") (pintype "passive"))
      (node (ref "C8") (pin "1") (pinfunction "1_1") (pintype "passive"))
      (node (ref "C9") (pin "1") (pinfunction "1_1") (pintype "passive"))
      (node (ref "IC1") (pin "K13") (pinfunction "VDD01_K13") (pintype "passive"))
      (node (ref "IC1") (pin "K15") (pinfunction "VDD02_K15") (pintype "passive"))
      (node (ref "IC1") (pin "K17") (pinfunction "VDD03_K17") (pintype "passive"))
      (node (ref "IC1") (pin "L10") (pinfunction "VDD04_L10") (pintype "passive"))
      (node (ref "IC1") (pin "L12") (pinfunction "VDD05_L12") (pintype "passive"))
      (node (ref "IC1") (pin "L14") (pinfunction "VDD06_L14") (pintype "passive"))
      (node (ref "IC1") (pin "L16") (pinfunction "VDD07_L16") (pintype "passive"))
      (node (ref "IC1") (pin "M11") (pinfunction "VDD09_M11") (pintype "passive"))
      (node (ref "IC1") (pin "M13") (pinfunction "VDD10_M13") (pintype "passive"))
      (node (ref "IC1") (pin "M15") (pinfunction "VDD11_M15") (pintype "passive"))
      (node (ref "IC1") (pin "M17") (pinfunction "VDD12_M17") (pintype "passive"))
      (node (ref "IC1") (pin "M9") (pinfunction "VDD08_M9") (pintype "passive"))
      (node (ref "IC1") (pin "N10") (pinfunction "VDD14_N10") (pintype "passive"))
      (node (ref "IC1") (pin "N12") (pinfunction "VDD15_N12") (pintype "passive"))
      (node (ref "IC1") (pin "N14") (pinfunction "VDD16_N14") (pintype "passive"))
      (node (ref "IC1") (pin "N16") (pinfunction "VDD17_N16") (pintype "passive"))
      (node (ref "IC1") (pin "N8") (pinfunction "VDD13_N8") (pintype "passive"))
      (node (ref "IC1") (pin "P11") (pinfunction "VDD19_P11") (pintype "passive"))
      (node (ref "IC1") (pin "P13") (pinfunction "VDD20_P13") (pintype "passive"))
      (node (ref "IC1") (pin "P15") (pinfunction "VDD21_P15") (pintype "passive"))
      (node (ref "IC1") (pin "P17") (pinfunction "VDD22_P17") (pintype "passive"))
      (node (ref "IC1") (pin "P9") (pinfunction "VDD18_P9") (pintype "passive"))
      (node (ref "IC1") (pin "R10") (pinfunction "VDD24_R10") (pintype "passive"))
      (node (ref "IC1") (pin "R12") (pinfunction "VDD25_R12") (pintype "passive"))
      (node (ref "IC1") (pin "R14") (pinfunction "VDD26_R14") (pintype "passive"))
      (node (ref "IC1") (pin "R16") (pinfunction "VDD27_R16") (pintype "passive"))
      (node (ref "IC1") (pin "R18") (pinfunction "VDD28_R18") (pintype "passive"))
      (node (ref "IC1") (pin "R8") (pinfunction "VDD23_R8") (pintype "passive"))
      (node (ref "IC1") (pin "T11") (pinfunction "VDD30_T11") (pintype "passive"))
      (node (ref "IC1") (pin "T13") (pinfunction "VDD31_T13") (pintype "passive"))
      (node (ref "IC1") (pin "T9") (pinfunction "VDD29_T9") (pintype "passive"))
      (node (ref "IC1") (pin "U10") (pinfunction "VDD33_U10") (pintype "passive"))
      (node (ref "IC1") (pin "U8") (pinfunction "VDD32_U8") (pintype "passive"))
      (node (ref "L1") (pin "2") (pinfunction "2_2") (pintype "passive"))
      (node (ref "L10") (pin "1") (pinfunction "1_1") (pintype "passive"))
      (node (ref "L2") (pin "2") (pinfunction "2_2") (pintype "passive"))
      (node (ref "L8") (pin "1") (pinfunction "1_1") (pintype "passive"))
      (node (ref "P1") (pin "2") (pinfunction "2_2") (pintype "passive"))
      (node (ref "P4") (pin "2") (pinfunction "2_2") (pintype "passive"))
    )
    (net (code "5") (name "+GVDD") (class "Default")
      (node (ref "C100") (pin "2") (pinfunction "2_2") (pintype "passive"))
      (node (ref "C101") (pin "2") (pinfunction "2_2") (pintype "passive"))
      (node (ref "C102") (pin "2") (pinfunction "2_2") (pintype "passive"))
      (node (ref "C103") (pin "2") (pinfunction "2_2") (pintype "passive"))
      (node (ref "C104") (pin "2") (pinfunction "2_2") (pintype "passive"))
      (node (ref "C105") (pin "2") (pinfunction "2_2") (pintype "passive"))
      (node (ref "C106") (pin "2") (pinfunction "2_2") (pintype "passive"))
      (node (ref "C107") (pin "2") (pinfunction "2_2") (pintype "passive"))
      (node (ref "C108") (pin "2") (pinfunction "2_2") (pintype "passive"))
      (node (ref "C109") (pin "2") (pinfunction "2_2") (pintype "passive"))
      (node (ref "C110") (pin "2") (pinfunction "2_2") (pintype "passive"))
      (node (ref "C74") (pin "1") (pinfunction "1_1") (pintype "passive"))
      (node (ref "C75") (pin "1") (pinfunction "1_1") (pintype "passive"))
      (node (ref "C76") (pin "1") (pinfunction "1_1") (pintype "passive"))
      (node (ref "C77") (pin "1") (pinfunction "1_1") (pintype "passive"))
      (node (ref "C78") (pin "1") (pinfunction "1_1") (pintype "passive"))
      (node (ref "C79") (pin "1") (pinfunction "1_1") (pintype "passive"))
      (node (ref "C80") (pin "1") (pinfunction "1_1") (pintype "passive"))
      (node (ref "C81") (pin "1") (pinfunction "1_1") (pintype "passive"))
      (node (ref "C82") (pin "1") (pinfunction "1_1") (pintype "passive"))
      (node (ref "C83") (pin "2") (pinfunction "2_2") (pintype "passive"))
      (node (ref "C84") (pin "2") (pinfunction "2_2") (pintype "passive"))
      (node (ref "C85") (pin "2") (pinfunction "2_2") (pintype "passive"))
      (node (ref "C86") (pin "2") (pinfunction "2_2") (pintype "passive"))
      (node (ref "C87") (pin "2") (pinfunction "2_2") (pintype "passive"))
      (node (ref "C88") (pin "2") (pinfunction "2_2") (pintype "passive"))
      (node (ref "C89") (pin "2") (pinfunction "2_2") (pintype "passive"))
      (node (ref "C90") (pin "2") (pinfunction "2_2") (pintype "passive"))
      (node (ref "C91") (pin "2") (pinfunction "2_2") (pintype "passive"))
      (node (ref "C92") (pin "2") (pinfunction "2_2") (pintype "passive"))
      (node (ref "C93") (pin "2") (pinfunction "2_2") (pintype "passive"))
      (node (ref "C94") (pin "2") (pinfunction "2_2") (pintype "passive"))
      (node (ref "IC1") (pin "AA20") (pinfunction "G1VDD18_AA20") (pintype "passive"))
      (node (ref "IC1") (pin "AB22") (pinfunction "G1VDD19_AB22") (pintype "passive"))
      (node (ref "IC1") (pin "AB24") (pinfunction "G1VDD20_AB24") (pintype "passive"))
      (node (ref "IC1") (pin "AD22") (pinfunction "G1VDD21_AD22") (pintype "passive"))
      (node (ref "IC1") (pin "AD24") (pinfunction "G1VDD23_AD24") (pintype "passive"))
      (node (ref "IC1") (pin "AD25") (pinfunction "G1VDD22_AD25") (pintype "passive"))
      (node (ref "IC1") (pin "J18") (pinfunction "G1VDD01_J18") (pintype "passive"))
      (node (ref "IC1") (pin "K18") (pinfunction "G1VDD02_K18") (pintype "passive"))
      (node (ref "IC1") (pin "K20") (pinfunction "G1VDD03_K20") (pintype "passive"))
      (node (ref "IC1") (pin "L18") (pinfunction "G1VDD04_L18") (pintype "passive"))
      (node (ref "IC1") (pin "M18") (pinfunction "G1VDD05_M18") (pintype "passive"))
      (node (ref "IC1") (pin "M20") (pinfunction "G1VDD06_M20") (pintype "passive"))
      (node (ref "IC1") (pin "N18") (pinfunction "G1VDD07_N18") (pintype "passive"))
      (node (ref "IC1") (pin "P18") (pinfunction "G1VDD08_P18") (pintype "passive"))
      (node (ref "IC1") (pin "P20") (pinfunction "G1VDD09_P20") (pintype "passive"))
      (node (ref "IC1") (pin "R21") (pinfunction "G1VDD10_R21") (pintype "passive"))
      (node (ref "IC1") (pin "R23") (pinfunction "G1VDD11_R23") (pintype "passive"))
      (node (ref "IC1") (pin "T22") (pinfunction "G1VDD12_T22") (pintype "passive"))
      (node (ref "IC1") (pin "T24") (pinfunction "G1VDD13_T24") (pintype "passive"))
      (node (ref "IC1") (pin "V22") (pinfunction "G1VDD14_V22") (pintype "passive"))
      (node (ref "IC1") (pin "V24") (pinfunction "G1VDD15_V24") (pintype "passive"))
      (node (ref "IC1") (pin "Y22") (pinfunction "G1VDD16_Y22") (pintype "passive"))
      (node (ref "IC1") (pin "Y24") (pinfunction "G1VDD17_Y24") (pintype "passive"))
    )
    (net (code "6") (name "/AVDD_CGA1") (class "Default")
      (node (ref "C143") (pin "2") (pinfunction "2_2") (pintype "passive"))
      (node (ref "C144") (pin "1") (pinfunction "1_1") (pintype "passive"))
      (node (ref "IC1") (pin "G12") (pinfunction "AVDD_CGA1_G12") (pintype "passive"))
      (node (ref "R8") (pin "2") (pinfunction "2_2") (pintype "passive"))
    )
    (net (code "7") (name "/AVDD_CGA2") (class "Default")
      (node (ref "C148") (pin "2") (pinfunction "2_2") (pintype "passive"))
      (node (ref "C149") (pin "1") (pinfunction "1_1") (pintype "passive"))
      (node (ref "IC1") (pin "G11") (pinfunction "AVDD_CGA2_G11") (pintype "passive"))
      (node (ref "R9") (pin "2") (pinfunction "2_2") (pintype "passive"))
    )
    (net (code "8") (name "/AVDD_DDR1") (class "Default")
      (node (ref "C155") (pin "2") (pinfunction "2_2") (pintype "passive"))
      (node (ref "C156") (pin "1") (pinfunction "1_1") (pintype "passive"))
      (node (ref "IC1") (pin "T19") (pinfunction "AVDD_D1_T19") (pintype "passive"))
      (node (ref "R13") (pin "2") (pinfunction "2_2") (pintype "passive"))
    )
    (net (code "9") (name "/AVDD_PLAT") (class "Default")
      (node (ref "C153") (pin "2") (pinfunction "2_2") (pintype "passive"))
      (node (ref "C154") (pin "1") (pinfunction "1_1") (pintype "passive"))
      (node (ref "IC1") (pin "G13") (pinfunction "AVDD_PLAT_G13") (pintype "passive"))
      (node (ref "R12") (pin "2") (pinfunction "2_2") (pintype "passive"))
    )
    (net (code "10") (name "/AVDD_SRDS1_PLL1") (class "Default")
      (node (ref "C145") (pin "1") (pinfunction "1_1") (pintype "passive"))
      (node (ref "C146") (pin "1") (pinfunction "1_1") (pintype "passive"))
      (node (ref "C147") (pin "1") (pinfunction "1_1") (pintype "passive"))
      (node (ref "IC1") (pin "W12") (pinfunction "AVDD_SD1_PLL1_W12") (pintype "passive"))
      (node (ref "R10") (pin "2") (pinfunction "2_2") (pintype "passive"))
    )
    (net (code "11") (name "/AVDD_SRDS1_PLL2") (class "Default")
      (node (ref "C150") (pin "1") (pinfunction "1_1") (pintype "passive"))
      (node (ref "C151") (pin "1") (pinfunction "1_1") (pintype "passive"))
      (node (ref "C152") (pin "1") (pinfunction "1_1") (pintype "passive"))
      (node (ref "IC1") (pin "V19") (pinfunction "AVDD_SD1_PLL2_V19") (pintype "passive"))
      (node (ref "R11") (pin "2") (pinfunction "2_2") (pintype "passive"))
    )
    (net (code "12") (name "/CPU_GND_SENSE") (class "Default")
      (node (ref "R2") (pin "2") (pinfunction "2_2") (pintype "passive"))
    )
    (net (code "13") (name "/CPU_VDD_SENSE") (class "Default")
      (node (ref "R1") (pin "2") (pinfunction "2_2") (pintype "passive"))
    )
    (net (code "14") (name "/PU_PWR_PROG_MTR") (class "Default")
      (node (ref "C111") (pin "2") (pinfunction "2_2") (pintype "passive"))
      (node (ref "IC1") (pin "G14") (pinfunction "PROG_MTR_G14") (pintype "passive"))
      (node (ref "P3") (pin "1") (pinfunction "1_1") (pintype "passive"))
      (node (ref "R5") (pin "2") (pinfunction "2_2") (pintype "passive"))
    )
    (net (code "15") (name "/PU_PWR_PROG_SFP") (class "Default")
      (node (ref "C112") (pin "2") (pinfunction "2_2") (pintype "passive"))
      (node (ref "IC1") (pin "F14") (pinfunction "TA_PROG_SFP_F14") (pintype "passive"))
      (node (ref "P2") (pin "2") (pinfunction "2_2") (pintype "passive"))
      (node (ref "R6") (pin "2") (pinfunction "2_2") (pintype "passive"))
    )
    (net (code "16") (name "EVDD") (class "Default")
      (node (ref "C98") (pin "2") (pinfunction "2_2") (pintype "passive"))
      (node (ref "C99") (pin "1") (pinfunction "1_1") (pintype "passive"))
      (node (ref "IC1") (pin "M8") (pinfunction "EVDD_M8") (pintype "passive"))
      (node (ref "L5") (pin "1") (pinfunction "1_1") (pintype "passive"))
      (node (ref "L6") (pin "1") (pinfunction "1_1") (pintype "passive"))
    )
    (net (code "17") (name "GND") (class "Default")
      (node (ref "C10") (pin "2") (pinfunction "2_2") (pintype "passive"))
      (node (ref "C100") (pin "1") (pinfunction "1_1") (pintype "passive"))
      (node (ref "C101") (pin "1") (pinfunction "1_1") (pintype "passive"))
      (node (ref "C102") (pin "1") (pinfunction "1_1") (pintype "passive"))
      (node (ref "C103") (pin "1") (pinfunction "1_1") (pintype "passive"))
      (node (ref "C104") (pin "1") (pinfunction "1_1") (pintype "passive"))
      (node (ref "C105") (pin "1") (pinfunction "1_1") (pintype "passive"))
      (node (ref "C106") (pin "1") (pinfunction "1_1") (pintype "passive"))
      (node (ref "C107") (pin "1") (pinfunction "1_1") (pintype "passive"))
      (node (ref "C108") (pin "1") (pinfunction "1_1") (pintype "passive"))
      (node (ref "C109") (pin "1") (pinfunction "1_1") (pintype "passive"))
      (node (ref "C11") (pin "2") (pinfunction "2_2") (pintype "passive"))
      (node (ref "C110") (pin "1") (pinfunction "1_1") (pintype "passive"))
      (node (ref "C111") (pin "1") (pinfunction "1_1") (pintype "passive"))
      (node (ref "C112") (pin "1") (pinfunction "1_1") (pintype "passive"))
      (node (ref "C113") (pin "1") (pinfunction "1_1") (pintype "passive"))
      (node (ref "C114") (pin "2") (pinfunction "2_2") (pintype "passive"))
      (node (ref "C116") (pin "2") (pinfunction "2_2") (pintype "passive"))
      (node (ref "C117") (pin "2") (pinfunction "2_2") (pintype "passive"))
      (node (ref "C118") (pin "1") (pinfunction "1_1") (pintype "passive"))
      (node (ref "C119") (pin "1") (pinfunction "1_1") (pintype "passive"))
      (node (ref "C12") (pin "2") (pinfunction "2_2") (pintype "passive"))
      (node (ref "C120") (pin "1") (pinfunction "1_1") (pintype "passive"))
      (node (ref "C124") (pin "1") (pinfunction "1_1") (pintype "passive"))
      (node (ref "C125") (pin "1") (pinfunction "1_1") (pintype "passive"))
      (node (ref "C126") (pin "2") (pinfunction "2_2") (pintype "passive"))
      (node (ref "C127") (pin "2") (pinfunction "2_2") (pintype "passive"))
      (node (ref "C128") (pin "1") (pinfunction "1_1") (pintype "passive"))
      (node (ref "C129") (pin "1") (pinfunction "1_1") (pintype "passive"))
      (node (ref "C13") (pin "2") (pinfunction "2_2") (pintype "passive"))
      (node (ref "C130") (pin "1") (pinfunction "1_1") (pintype "passive"))
      (node (ref "C131") (pin "1") (pinfunction "1_1") (pintype "passive"))
      (node (ref "C132") (pin "1") (pinfunction "1_1") (pintype "passive"))
      (node (ref "C133") (pin "1") (pinfunction "1_1") (pintype "passive"))
      (node (ref "C134") (pin "1") (pinfunction "1_1") (pintype "passive"))
      (node (ref "C135") (pin "1") (pinfunction "1_1") (pintype "passive"))
      (node (ref "C136") (pin "2") (pinfunction "2_2") (pintype "passive"))
      (node (ref "C137") (pin "2") (pinfunction "2_2") (pintype "passive"))
      (node (ref "C138") (pin "2") (pinfunction "2_2") (pintype "passive"))
      (node (ref "C139") (pin "2") (pinfunction "2_2") (pintype "passive"))
      (node (ref "C14") (pin "1") (pinfunction "1_1") (pintype "passive"))
      (node (ref "C140") (pin "2") (pinfunction "2_2") (pintype "passive"))
      (node (ref "C141") (pin "1") (pinfunction "1_1") (pintype "passive"))
      (node (ref "C142") (pin "1") (pinfunction "1_1") (pintype "passive"))
      (node (ref "C143") (pin "1") (pinfunction "1_1") (pintype "passive"))
      (node (ref "C144") (pin "2") (pinfunction "2_2") (pintype "passive"))
      (node (ref "C145") (pin "2") (pinfunction "2_2") (pintype "passive"))
      (node (ref "C146") (pin "2") (pinfunction "2_2") (pintype "passive"))
      (node (ref "C147") (pin "2") (pinfunction "2_2") (pintype "passive"))
      (node (ref "C148") (pin "1") (pinfunction "1_1") (pintype "passive"))
      (node (ref "C149") (pin "2") (pinfunction "2_2") (pintype "passive"))
      (node (ref "C15") (pin "1") (pinfunction "1_1") (pintype "passive"))
      (node (ref "C150") (pin "2") (pinfunction "2_2") (pintype "passive"))
      (node (ref "C151") (pin "2") (pinfunction "2_2") (pintype "passive"))
      (node (ref "C152") (pin "2") (pinfunction "2_2") (pintype "passive"))
      (node (ref "C153") (pin "1") (pinfunction "1_1") (pintype "passive"))
      (node (ref "C154") (pin "2") (pinfunction "2_2") (pintype "passive"))
      (node (ref "C155") (pin "1") (pinfunction "1_1") (pintype "passive"))
      (node (ref "C156") (pin "2") (pinfunction "2_2") (pintype "passive"))
      (node (ref "C16") (pin "1") (pinfunction "1_1") (pintype "passive"))
      (node (ref "C17") (pin "1") (pinfunction "1_1") (pintype "passive"))
      (node (ref "C18") (pin "1") (pinfunction "1_1") (pintype "passive"))
      (node (ref "C19") (pin "1") (pinfunction "1_1") (pintype "passive"))
      (node (ref "C20") (pin "1") (pinfunction "1_1") (pintype "passive"))
      (node (ref "C21") (pin "1") (pinfunction "1_1") (pintype "passive"))
      (node (ref "C22") (pin "1") (pinfunction "1_1") (pintype "passive"))
      (node (ref "C23") (pin "1") (pinfunction "1_1") (pintype "passive"))
      (node (ref "C24") (pin "2") (pinfunction "2_2") (pintype "passive"))
      (node (ref "C25") (pin "2") (pinfunction "2_2") (pintype "passive"))
      (node (ref "C26") (pin "2") (pinfunction "2_2") (pintype "passive"))
      (node (ref "C27") (pin "1") (pinfunction "1_1") (pintype "passive"))
      (node (ref "C28") (pin "1") (pinfunction "1_1") (pintype "passive"))
      (node (ref "C29") (pin "2") (pinfunction "2_2") (pintype "passive"))
      (node (ref "C30") (pin "1") (pinfunction "1_1") (pintype "passive"))
      (node (ref "C31") (pin "1") (pinfunction "1_1") (pintype "passive"))
      (node (ref "C32") (pin "1") (pinfunction "1_1") (pintype "passive"))
      (node (ref "C33") (pin "1") (pinfunction "1_1") (pintype "passive"))
      (node (ref "C34") (pin "1") (pinfunction "1_1") (pintype "passive"))
      (node (ref "C35") (pin "1") (pinfunction "1_1") (pintype "passive"))
      (node (ref "C36") (pin "1") (pinfunction "1_1") (pintype "passive"))
      (node (ref "C37") (pin "1") (pinfunction "1_1") (pintype "passive"))
      (node (ref "C38") (pin "1") (pinfunction "1_1") (pintype "passive"))
      (node (ref "C39") (pin "1") (pinfunction "1_1") (pintype "passive"))
      (node (ref "C40") (pin "1") (pinfunction "1_1") (pintype "passive"))
      (node (ref "C41") (pin "2") (pinfunction "2_2") (pintype "passive"))
      (node (ref "C42") (pin "2") (pinfunction "2_2") (pintype "passive"))
      (node (ref "C43") (pin "2") (pinfunction "2_2") (pintype "passive"))
      (node (ref "C44") (pin "1") (pinfunction "1_1") (pintype "passive"))
      (node (ref "C45") (pin "1") (pinfunction "1_1") (pintype "passive"))
      (node (ref "C46") (pin "2") (pinfunction "2_2") (pintype "passive"))
      (node (ref "C47") (pin "1") (pinfunction "1_1") (pintype "passive"))
      (node (ref "C48") (pin "1") (pinfunction "1_1") (pintype "passive"))
      (node (ref "C49") (pin "1") (pinfunction "1_1") (pintype "passive"))
      (node (ref "C5") (pin "2") (pinfunction "2_2") (pintype "passive"))
      (node (ref "C50") (pin "1") (pinfunction "1_1") (pintype "passive"))
      (node (ref "C51") (pin "1") (pinfunction "1_1") (pintype "passive"))
      (node (ref "C52") (pin "1") (pinfunction "1_1") (pintype "passive"))
      (node (ref "C53") (pin "1") (pinfunction "1_1") (pintype "passive"))
      (node (ref "C54") (pin "1") (pinfunction "1_1") (pintype "passive"))
      (node (ref "C55") (pin "1") (pinfunction "1_1") (pintype "passive"))
      (node (ref "C56") (pin "1") (pinfunction "1_1") (pintype "passive"))
      (node (ref "C57") (pin "1") (pinfunction "1_1") (pintype "passive"))
      (node (ref "C58") (pin "2") (pinfunction "2_2") (pintype "passive"))
      (node (ref "C59") (pin "2") (pinfunction "2_2") (pintype "passive"))
      (node (ref "C6") (pin "2") (pinfunction "2_2") (pintype "passive"))
      (node (ref "C60") (pin "2") (pinfunction "2_2") (pintype "passive"))
      (node (ref "C61") (pin "2") (pinfunction "2_2") (pintype "passive"))
      (node (ref "C62") (pin "1") (pinfunction "1_1") (pintype "passive"))
      (node (ref "C63") (pin "1") (pinfunction "1_1") (pintype "passive"))
      (node (ref "C64") (pin "2") (pinfunction "2_2") (pintype "passive"))
      (node (ref "C65") (pin "1") (pinfunction "1_1") (pintype "passive"))
      (node (ref "C66") (pin "1") (pinfunction "1_1") (pintype "passive"))
      (node (ref "C67") (pin "1") (pinfunction "1_1") (pintype "passive"))
      (node (ref "C68") (pin "1") (pinfunction "1_1") (pintype "passive"))
      (node (ref "C69") (pin "1") (pinfunction "1_1") (pintype "passive"))
      (node (ref "C7") (pin "2") (pinfunction "2_2") (pintype "passive"))
      (node (ref "C70") (pin "1") (pinfunction "1_1") (pintype "passive"))
      (node (ref "C71") (pin "1") (pinfunction "1_1") (pintype "passive"))
      (node (ref "C72") (pin "2") (pinfunction "2_2") (pintype "passive"))
      (node (ref "C73") (pin "2") (pinfunction "2_2") (pintype "passive"))
      (node (ref "C74") (pin "2") (pinfunction "2_2") (pintype "passive"))
      (node (ref "C75") (pin "2") (pinfunction "2_2") (pintype "passive"))
      (node (ref "C76") (pin "2") (pinfunction "2_2") (pintype "passive"))
      (node (ref "C77") (pin "2") (pinfunction "2_2") (pintype "passive"))
      (node (ref "C78") (pin "2") (pinfunction "2_2") (pintype "passive"))
      (node (ref "C79") (pin "2") (pinfunction "2_2") (pintype "passive"))
      (node (ref "C8") (pin "2") (pinfunction "2_2") (pintype "passive"))
      (node (ref "C80") (pin "2") (pinfunction "2_2") (pintype "passive"))
      (node (ref "C81") (pin "2") (pinfunction "2_2") (pintype "passive"))
      (node (ref "C82") (pin "2") (pinfunction "2_2") (pintype "passive"))
      (node (ref "C83") (pin "1") (pinfunction "1_1") (pintype "passive"))
      (node (ref "C84") (pin "1") (pinfunction "1_1") (pintype "passive"))
      (node (ref "C85") (pin "1") (pinfunction "1_1") (pintype "passive"))
      (node (ref "C86") (pin "1") (pinfunction "1_1") (pintype "passive"))
      (node (ref "C87") (pin "1") (pinfunction "1_1") (pintype "passive"))
      (node (ref "C88") (pin "1") (pinfunction "1_1") (pintype "passive"))
      (node (ref "C89") (pin "1") (pinfunction "1_1") (pintype "passive"))
      (node (ref "C9") (pin "2") (pinfunction "2_2") (pintype "passive"))
      (node (ref "C90") (pin "1") (pinfunction "1_1") (pintype "passive"))
      (node (ref "C91") (pin "1") (pinfunction "1_1") (pintype "passive"))
      (node (ref "C92") (pin "1") (pinfunction "1_1") (pintype "passive"))
      (node (ref "C93") (pin "1") (pinfunction "1_1") (pintype "passive"))
      (node (ref "C94") (pin "1") (pinfunction "1_1") (pintype "passive"))
      (node (ref "C95") (pin "1") (pinfunction "1_1") (pintype "passive"))
      (node (ref "C96") (pin "1") (pinfunction "1_1") (pintype "passive"))
      (node (ref "C97") (pin "2") (pinfunction "2_2") (pintype "passive"))
      (node (ref "C98") (pin "1") (pinfunction "1_1") (pintype "passive"))
      (node (ref "C99") (pin "2") (pinfunction "2_2") (pintype "passive"))
      (node (ref "IC1") (pin "A2") (pinfunction "GND001_A2") (pintype "passive"))
      (node (ref "IC1") (pin "A24") (pinfunction "GND003_A24") (pintype "passive"))
      (node (ref "IC1") (pin "A5") (pinfunction "GND002_A5") (pintype "passive"))
      (node (ref "IC1") (pin "AB2") (pinfunction "GND135_AB2") (pintype "passive"))
      (node (ref "IC1") (pin "AB4") (pinfunction "GND136_AB4") (pintype "passive"))
      (node (ref "IC1") (pin "AD1") (pinfunction "GND137_AD1") (pintype "passive"))
      (node (ref "IC1") (pin "AD4") (pinfunction "GND138_AD4") (pintype "passive"))
      (node (ref "IC1") (pin "AE2") (pinfunction "GND139_AE2") (pintype "passive"))
      (node (ref "IC1") (pin "B10") (pinfunction "GND007_B10") (pintype "passive"))
      (node (ref "IC1") (pin "B13") (pinfunction "GND008_B13") (pintype "passive"))
      (node (ref "IC1") (pin "B16") (pinfunction "GND009_B16") (pintype "passive"))
      (node (ref "IC1") (pin "B19") (pinfunction "GND010_B19") (pintype "passive"))
      (node (ref "IC1") (pin "B21") (pinfunction "GND011_B21") (pintype "passive"))
      (node (ref "IC1") (pin "B25") (pinfunction "GND012_B25") (pintype "passive"))
      (node (ref "IC1") (pin "B3") (pinfunction "GND004_B3") (pintype "passive"))
      (node (ref "IC1") (pin "B4") (pinfunction "GND005_B4") (pintype "passive"))
      (node (ref "IC1") (pin "B7") (pinfunction "GND006_B7") (pintype "passive"))
      (node (ref "IC1") (pin "C1") (pinfunction "GND013_C1") (pintype "passive"))
      (node (ref "IC1") (pin "C2") (pinfunction "GND014_C2") (pintype "passive"))
      (node (ref "IC1") (pin "C23") (pinfunction "GND016_C23") (pintype "passive"))
      (node (ref "IC1") (pin "C5") (pinfunction "GND015_C5") (pintype "passive"))
      (node (ref "IC1") (pin "D12") (pinfunction "GND021_D12") (pintype "passive"))
      (node (ref "IC1") (pin "D15") (pinfunction "GND022_D15") (pintype "passive"))
      (node (ref "IC1") (pin "D18") (pinfunction "GND023_D18") (pintype "passive"))
      (node (ref "IC1") (pin "D21") (pinfunction "GND024_D21") (pintype "passive"))
      (node (ref "IC1") (pin "D3") (pinfunction "GND017_D3") (pintype "passive"))
      (node (ref "IC1") (pin "D4") (pinfunction "GND018_D4") (pintype "passive"))
      (node (ref "IC1") (pin "D7") (pinfunction "GND019_D7") (pintype "passive"))
      (node (ref "IC1") (pin "D9") (pinfunction "GND020_D9") (pintype "passive"))
      (node (ref "IC1") (pin "E1") (pinfunction "GND025_E1") (pintype "passive"))
      (node (ref "IC1") (pin "E2") (pinfunction "GND026_E2") (pintype "passive"))
      (node (ref "IC1") (pin "E22") (pinfunction "GND028_E22") (pintype "passive"))
      (node (ref "IC1") (pin "E24") (pinfunction "GND029_E24") (pintype "passive"))
      (node (ref "IC1") (pin "E5") (pinfunction "GND027_E5") (pintype "passive"))
      (node (ref "IC1") (pin "F11") (pinfunction "GND034_F11") (pintype "passive"))
      (node (ref "IC1") (pin "F12") (pinfunction "GND035_F12") (pintype "passive"))
      (node (ref "IC1") (pin "F13") (pinfunction "GND036_F13") (pintype "passive"))
      (node (ref "IC1") (pin "F17") (pinfunction "GND037_F17") (pintype "passive"))
      (node (ref "IC1") (pin "F20") (pinfunction "GND038_F20") (pintype "passive"))
      (node (ref "IC1") (pin "F3") (pinfunction "GND030_F3") (pintype "passive"))
      (node (ref "IC1") (pin "F4") (pinfunction "GND031_F4") (pintype "passive"))
      (node (ref "IC1") (pin "F7") (pinfunction "GND032_F7") (pintype "passive"))
      (node (ref "IC1") (pin "F8") (pinfunction "GND033_F8") (pintype "passive"))
      (node (ref "IC1") (pin "G1") (pinfunction "GND039_G1") (pintype "passive"))
      (node (ref "IC1") (pin "G2") (pinfunction "GND040_G2") (pintype "passive"))
      (node (ref "IC1") (pin "G22") (pinfunction "GND041_G22") (pintype "passive"))
      (node (ref "IC1") (pin "G24") (pinfunction "GND042_G24") (pintype "passive"))
      (node (ref "IC1") (pin "H10") (pinfunction "GND048_H10") (pintype "passive"))
      (node (ref "IC1") (pin "H11") (pinfunction "GND049_H11") (pintype "passive"))
      (node (ref "IC1") (pin "H12") (pinfunction "GND050_H12") (pintype "passive"))
      (node (ref "IC1") (pin "H13") (pinfunction "GND051_H13") (pintype "passive"))
      (node (ref "IC1") (pin "H14") (pinfunction "GND052_H14") (pintype "passive"))
      (node (ref "IC1") (pin "H15") (pinfunction "GND053_H15") (pintype "passive"))
      (node (ref "IC1") (pin "H16") (pinfunction "GND054_H16") (pintype "passive"))
      (node (ref "IC1") (pin "H17") (pinfunction "GND055_H17") (pintype "passive"))
      (node (ref "IC1") (pin "H3") (pinfunction "GND043_H3") (pintype "passive"))
      (node (ref "IC1") (pin "H4") (pinfunction "GND044_H4") (pintype "passive"))
      (node (ref "IC1") (pin "H5") (pinfunction "GND045_H5") (pintype "passive"))
      (node (ref "IC1") (pin "H8") (pinfunction "GND046_H8") (pintype "passive"))
      (node (ref "IC1") (pin "H9") (pinfunction "GND047_H9") (pintype "passive"))
      (node (ref "IC1") (pin "J19") (pinfunction "GND057_J19") (pintype "passive"))
      (node (ref "IC1") (pin "J20") (pinfunction "GND058_J20") (pintype "passive"))
      (node (ref "IC1") (pin "J24") (pinfunction "GND059_J24") (pintype "passive"))
      (node (ref "IC1") (pin "J7") (pinfunction "GND056_J7") (pintype "passive"))
      (node (ref "IC1") (pin "K10") (pinfunction "GND063_K10") (pintype "passive"))
      (node (ref "IC1") (pin "K12") (pinfunction "GND064_K12") (pintype "passive"))
      (node (ref "IC1") (pin "K14") (pinfunction "GND065_K14") (pintype "passive"))
      (node (ref "IC1") (pin "K16") (pinfunction "GND066_K16") (pintype "passive"))
      (node (ref "IC1") (pin "K19") (pinfunction "GND067_K19") (pintype "passive"))
      (node (ref "IC1") (pin "K2") (pinfunction "GND060_K2") (pintype "passive"))
      (node (ref "IC1") (pin "K22") (pinfunction "GND068_K22") (pintype "passive"))
      (node (ref "IC1") (pin "K4") (pinfunction "GND061_K4") (pintype "passive"))
      (node (ref "IC1") (pin "K7") (pinfunction "GND062_K7") (pintype "passive"))
      (node (ref "IC1") (pin "L11") (pinfunction "GND071_L11") (pintype "passive"))
      (node (ref "IC1") (pin "L13") (pinfunction "GND072_L13") (pintype "passive"))
      (node (ref "IC1") (pin "L15") (pinfunction "GND073_L15") (pintype "passive"))
      (node (ref "IC1") (pin "L17") (pinfunction "GND074_L17") (pintype "passive"))
      (node (ref "IC1") (pin "L19") (pinfunction "GND075_L19") (pintype "passive"))
      (node (ref "IC1") (pin "L20") (pinfunction "GND076_L20") (pintype "passive"))
      (node (ref "IC1") (pin "L24") (pinfunction "GND077_L24") (pintype "passive"))
      (node (ref "IC1") (pin "L7") (pinfunction "GND069_L7") (pintype "passive"))
      (node (ref "IC1") (pin "L9") (pinfunction "GND070_L9") (pintype "passive"))
      (node (ref "IC1") (pin "M10") (pinfunction "GND079_M10") (pintype "passive"))
      (node (ref "IC1") (pin "M12") (pinfunction "GND080_M12") (pintype "passive"))
      (node (ref "IC1") (pin "M14") (pinfunction "GND081_M14") (pintype "passive"))
      (node (ref "IC1") (pin "M16") (pinfunction "GND082_M16") (pintype "passive"))
      (node (ref "IC1") (pin "M19") (pinfunction "GND083_M19") (pintype "passive"))
      (node (ref "IC1") (pin "M22") (pinfunction "GND084_M22") (pintype "passive"))
      (node (ref "IC1") (pin "M7") (pinfunction "GND078_M7") (pintype "passive"))
      (node (ref "IC1") (pin "N11") (pinfunction "GND089_N11") (pintype "passive"))
      (node (ref "IC1") (pin "N13") (pinfunction "GND090_N13") (pintype "passive"))
      (node (ref "IC1") (pin "N15") (pinfunction "GND091_N15") (pintype "passive"))
      (node (ref "IC1") (pin "N17") (pinfunction "GND092_N17") (pintype "passive"))
      (node (ref "IC1") (pin "N19") (pinfunction "GND093_N19") (pintype "passive"))
      (node (ref "IC1") (pin "N2") (pinfunction "GND085_N2") (pintype "passive"))
      (node (ref "IC1") (pin "N20") (pinfunction "GND094_N20") (pintype "passive"))
      (node (ref "IC1") (pin "N4") (pinfunction "GND086_N4") (pintype "passive"))
      (node (ref "IC1") (pin "N6") (pinfunction "GND087_N6") (pintype "passive"))
      (node (ref "IC1") (pin "N9") (pinfunction "GND088_N9") (pintype "passive"))
      (node (ref "IC1") (pin "P10") (pinfunction "GND097_P10") (pintype "passive"))
      (node (ref "IC1") (pin "P12") (pinfunction "GND098_P12") (pintype "passive"))
      (node (ref "IC1") (pin "P14") (pinfunction "GND099_P14") (pintype "passive"))
      (node (ref "IC1") (pin "P16") (pinfunction "GND100_P16") (pintype "passive"))
      (node (ref "IC1") (pin "P19") (pinfunction "GND101_P19") (pintype "passive"))
      (node (ref "IC1") (pin "P22") (pinfunction "GND102_P22") (pintype "passive"))
      (node (ref "IC1") (pin "P24") (pinfunction "GND103_P24") (pintype "passive"))
      (node (ref "IC1") (pin "P7") (pinfunction "GND095_P7") (pintype "passive"))
      (node (ref "IC1") (pin "P8") (pinfunction "GND096_P8") (pintype "passive"))
      (node (ref "IC1") (pin "R11") (pinfunction "GND105_R11") (pintype "passive"))
      (node (ref "IC1") (pin "R13") (pinfunction "GND106_R13") (pintype "passive"))
      (node (ref "IC1") (pin "R15") (pinfunction "GND107_R15") (pintype "passive"))
      (node (ref "IC1") (pin "R17") (pinfunction "GND108_R17") (pintype "passive"))
      (node (ref "IC1") (pin "R19") (pinfunction "GND109_R19") (pintype "passive"))
      (node (ref "IC1") (pin "R25") (pinfunction "GND110_R25") (pintype "passive"))
      (node (ref "IC1") (pin "R9") (pinfunction "GND104_R9") (pintype "passive"))
      (node (ref "IC1") (pin "T10") (pinfunction "GND114_T10") (pintype "passive"))
      (node (ref "IC1") (pin "T12") (pinfunction "GND115_T12") (pintype "passive"))
      (node (ref "IC1") (pin "T14") (pinfunction "GND116_T14") (pintype "passive"))
      (node (ref "IC1") (pin "T2") (pinfunction "GND111_T2") (pintype "passive"))
      (node (ref "IC1") (pin "T20") (pinfunction "GND117_T20") (pintype "passive"))
      (node (ref "IC1") (pin "T4") (pinfunction "GND112_T4") (pintype "passive"))
      (node (ref "IC1") (pin "T8") (pinfunction "GND113_T8") (pintype "passive"))
      (node (ref "IC1") (pin "U11") (pinfunction "GND120_U11") (pintype "passive"))
      (node (ref "IC1") (pin "U20") (pinfunction "GND121_U20") (pintype "passive"))
      (node (ref "IC1") (pin "U6") (pinfunction "GND118_U6") (pintype "passive"))
      (node (ref "IC1") (pin "U9") (pinfunction "GND119_U9") (pintype "passive"))
      (node (ref "IC1") (pin "V10") (pinfunction "GND125_V10") (pintype "passive"))
      (node (ref "IC1") (pin "V11") (pinfunction "GND126_V11") (pintype "passive"))
      (node (ref "IC1") (pin "V12") (pinfunction "GND127_V12") (pintype "passive"))
      (node (ref "IC1") (pin "V13") (pinfunction "GND128_V13") (pintype "passive"))
      (node (ref "IC1") (pin "V14") (pinfunction "GND129_V14") (pintype "passive"))
      (node (ref "IC1") (pin "V2") (pinfunction "GND122_V2") (pintype "passive"))
      (node (ref "IC1") (pin "V20") (pinfunction "GND130_V20") (pintype "passive"))
      (node (ref "IC1") (pin "V8") (pinfunction "GND123_V8") (pintype "passive"))
      (node (ref "IC1") (pin "V9") (pinfunction "GND124_V9") (pintype "passive"))
      (node (ref "IC1") (pin "W20") (pinfunction "GND132_W20") (pintype "passive"))
      (node (ref "IC1") (pin "W4") (pinfunction "GND131_W4") (pintype "passive"))
      (node (ref "IC1") (pin "Y2") (pinfunction "GND133_Y2") (pintype "passive"))
      (node (ref "IC1") (pin "Y20") (pinfunction "GND134_Y20") (pintype "passive"))
      (node (ref "R3") (pin "1") (pinfunction "1_1") (pintype "passive"))
      (node (ref "R4") (pin "1") (pinfunction "1_1") (pintype "passive"))
      (node (ref "R5") (pin "1") (pinfunction "1_1") (pintype "passive"))
      (node (ref "R6") (pin "1") (pinfunction "1_1") (pintype "passive"))
    )
    (net (code "18") (name "Net-(C1-Pad1)") (class "Default")
      (node (ref "C1") (pin "1") (pinfunction "1_1") (pintype "passive"))
      (node (ref "C2") (pin "1") (pinfunction "1_1") (pintype "passive"))
      (node (ref "C3") (pin "2") (pinfunction "2_2") (pintype "passive"))
      (node (ref "C4") (pin "1") (pinfunction "1_1") (pintype "passive"))
    )
    (net (code "19") (name "Net-(C115-Pad1)") (class "Default")
      (node (ref "C115") (pin "1") (pinfunction "1_1") (pintype "passive"))
      (node (ref "C123") (pin "1") (pinfunction "1_1") (pintype "passive"))
      (node (ref "R7") (pin "1") (pinfunction "1_1") (pintype "passive"))
    )
    (net (code "20") (name "Net-(C121-Pad1)") (class "Default")
      (node (ref "C121") (pin "1") (pinfunction "1_1") (pintype "passive"))
      (node (ref "C122") (pin "2") (pinfunction "2_2") (pintype "passive"))
    )
    (net (code "21") (name "Net-(IC1G-DVDD1)") (class "Default")
      (node (ref "C95") (pin "2") (pinfunction "2_2") (pintype "passive"))
      (node (ref "C96") (pin "2") (pinfunction "2_2") (pintype "passive"))
      (node (ref "C97") (pin "1") (pinfunction "1_1") (pintype "passive"))
      (node (ref "IC1") (pin "K8") (pinfunction "DVDD1_K8") (pintype "passive"))
      (node (ref "IC1") (pin "L8") (pinfunction "DVDD2_L8") (pintype "passive"))
    )
    (net (code "22") (name "Net-(IC1G-FA_VL)") (class "Default")
      (node (ref "C115") (pin "2") (pinfunction "2_2") (pintype "passive"))
      (node (ref "C123") (pin "2") (pinfunction "2_2") (pintype "passive"))
      (node (ref "IC1") (pin "R7") (pinfunction "FA_VL_R7") (pintype "passive"))
      (node (ref "P4") (pin "1") (pinfunction "1_1") (pintype "passive"))
      (node (ref "R7") (pin "2") (pinfunction "2_2") (pintype "passive"))
    )
    (net (code "23") (name "Net-(IC1G-LVDD1)") (class "Default")
      (node (ref "C116") (pin "1") (pinfunction "1_1") (pintype "passive"))
      (node (ref "C117") (pin "1") (pinfunction "1_1") (pintype "passive"))
      (node (ref "C118") (pin "2") (pinfunction "2_2") (pintype "passive"))
      (node (ref "C119") (pin "2") (pinfunction "2_2") (pintype "passive"))
      (node (ref "C120") (pin "2") (pinfunction "2_2") (pintype "passive"))
      (node (ref "IC1") (pin "U12") (pinfunction "LVDD1_U12") (pintype "passive"))
      (node (ref "IC1") (pin "U13") (pinfunction "LVDD2_U13") (pintype "passive"))
      (node (ref "IC1") (pin "U14") (pinfunction "LVDD3_U14") (pintype "passive"))
      (node (ref "L7") (pin "2") (pinfunction "2_2") (pintype "passive"))
    )
    (net (code "24") (name "Net-(IC1H-SENSEGND)") (class "Default")
      (node (ref "IC1") (pin "V7") (pinfunction "SENSEGND_V7") (pintype "passive"))
      (node (ref "R2") (pin "1") (pinfunction "1_1") (pintype "passive"))
    )
    (net (code "25") (name "Net-(IC1H-SENSEVDD)") (class "Default")
      (node (ref "IC1") (pin "W7") (pinfunction "SENSEVDD_W7") (pintype "passive"))
      (node (ref "R1") (pin "1") (pinfunction "1_1") (pintype "passive"))
    )
    (net (code "26") (name "Net-(IC1H-TVDD)") (class "Default")
      (node (ref "C63") (pin "2") (pinfunction "2_2") (pintype "passive"))
      (node (ref "C64") (pin "1") (pinfunction "1_1") (pintype "passive"))
      (node (ref "IC1") (pin "V6") (pinfunction "TVDD_V6") (pintype "passive"))
      (node (ref "L4") (pin "1") (pinfunction "1_1") (pintype "passive"))
    )
    (net (code "27") (name "Net-(IC1H-USB_HVDD1)") (class "Default")
      (node (ref "C44") (pin "2") (pinfunction "2_2") (pintype "passive"))
      (node (ref "C45") (pin "2") (pinfunction "2_2") (pintype "passive"))
      (node (ref "C46") (pin "1") (pinfunction "1_1") (pintype "passive"))
      (node (ref "C47") (pin "2") (pinfunction "2_2") (pintype "passive"))
      (node (ref "IC1") (pin "J8") (pinfunction "USB_HVDD1_J8") (pintype "passive"))
      (node (ref "IC1") (pin "J9") (pinfunction "USB_HVDD2_J9") (pintype "passive"))
      (node (ref "L3") (pin "1") (pinfunction "1_1") (pintype "passive"))
    )
    (net (code "28") (name "Net-(IC1H-USB_SDVDD1)") (class "Default")
      (node (ref "C27") (pin "2") (pinfunction "2_2") (pintype "passive"))
      (node (ref "C28") (pin "2") (pinfunction "2_2") (pintype "passive"))
      (node (ref "C29") (pin "1") (pinfunction "1_1") (pintype "passive"))
      (node (ref "C30") (pin "2") (pinfunction "2_2") (pintype "passive"))
      (node (ref "IC1") (pin "K11") (pinfunction "USB_SDVDD2_K11") (pintype "passive"))
      (node (ref "IC1") (pin "K9") (pinfunction "USB_SDVDD1_K9") (pintype "passive"))
      (node (ref "L2") (pin "1") (pinfunction "1_1") (pintype "passive"))
    )
    (net (code "29") (name "Net-(IC1H-USB_SVDD1)") (class "Default")
      (node (ref "C1") (pin "2") (pinfunction "2_2") (pintype "passive"))
      (node (ref "C2") (pin "2") (pinfunction "2_2") (pintype "passive"))
      (node (ref "C3") (pin "1") (pinfunction "1_1") (pintype "passive"))
      (node (ref "C4") (pin "2") (pinfunction "2_2") (pintype "passive"))
      (node (ref "IC1") (pin "J10") (pinfunction "USB_SVDD1_J10") (pintype "passive"))
      (node (ref "IC1") (pin "J11") (pinfunction "USB_SVDD2_J11") (pintype "passive"))
      (node (ref "L1") (pin "1") (pinfunction "1_1") (pintype "passive"))
    )
    (net (code "30") (name "PWR_X1VDD") (class "Default")
      (node (ref "C138") (pin "1") (pinfunction "1_1") (pintype "passive"))
      (node (ref "C139") (pin "1") (pinfunction "1_1") (pintype "passive"))
      (node (ref "C140") (pin "1") (pinfunction "1_1") (pintype "passive"))
      (node (ref "L11") (pin "2") (pinfunction "2_2") (pintype "passive"))
      (node (ref "L9") (pin "2") (pinfunction "2_2") (pintype "passive"))
    )
    (net (code "31") (name "S1VDD") (class "Default")
      (node (ref "C124") (pin "2") (pinfunction "2_2") (pintype "passive"))
      (node (ref "C125") (pin "2") (pinfunction "2_2") (pintype "passive"))
      (node (ref "C126") (pin "1") (pinfunction "1_1") (pintype "passive"))
      (node (ref "C127") (pin "1") (pinfunction "1_1") (pintype "passive"))
      (node (ref "C128") (pin "2") (pinfunction "2_2") (pintype "passive"))
      (node (ref "C129") (pin "2") (pinfunction "2_2") (pintype "passive"))
      (node (ref "C130") (pin "2") (pinfunction "2_2") (pintype "passive"))
      (node (ref "C131") (pin "2") (pinfunction "2_2") (pintype "passive"))
      (node (ref "IC1") (pin "T15") (pinfunction "S1VDD1_T15") (pintype "passive"))
      (node (ref "IC1") (pin "T16") (pinfunction "S1VDD2_T16") (pintype "passive"))
      (node (ref "IC1") (pin "T17") (pinfunction "S1VDD3_T17") (pintype "passive"))
      (node (ref "IC1") (pin "T18") (pinfunction "S1VDD4_T18") (pintype "passive"))
      (node (ref "IC1") (pin "W14") (pinfunction "S1VDD5_W14") (pintype "passive"))
      (node (ref "L10") (pin "2") (pinfunction "2_2") (pintype "passive"))
      (node (ref "L8") (pin "2") (pinfunction "2_2") (pintype "passive"))
    )
    (net (code "32") (name "VDD_LP") (class "Default")
      (node (ref "C61") (pin "1") (pinfunction "1_1") (pintype "passive"))
      (node (ref "C62") (pin "2") (pinfunction "2_2") (pintype "passive"))
      (node (ref "IC1") (pin "H20") (pinfunction "TA_BB_VDD_H20") (pintype "passive"))
      (node (ref "P1") (pin "1") (pinfunction "1_1") (pintype "passive"))
      (node (ref "R3") (pin "2") (pinfunction "2_2") (pintype "passive"))
    )
    (net (code "33") (name "X1VDD") (class "Default")
      (node (ref "C132") (pin "2") (pinfunction "2_2") (pintype "passive"))
      (node (ref "C133") (pin "2") (pinfunction "2_2") (pintype "passive"))
      (node (ref "C134") (pin "2") (pinfunction "2_2") (pintype "passive"))
      (node (ref "C135") (pin "2") (pinfunction "2_2") (pintype "passive"))
      (node (ref "C136") (pin "1") (pinfunction "1_1") (pintype "passive"))
      (node (ref "C137") (pin "1") (pinfunction "1_1") (pintype "passive"))
      (node (ref "C141") (pin "2") (pinfunction "2_2") (pintype "passive"))
      (node (ref "C142") (pin "2") (pinfunction "2_2") (pintype "passive"))
      (node (ref "IC1") (pin "W15") (pinfunction "X1VDD1_W15") (pintype "passive"))
      (node (ref "IC1") (pin "W16") (pinfunction "X1VDD2_W16") (pintype "passive"))
      (node (ref "IC1") (pin "W17") (pinfunction "X1VDD3_W17") (pintype "passive"))
      (node (ref "IC1") (pin "W18") (pinfunction "X1VDD4_W18") (pintype "passive"))
      (node (ref "IC1") (pin "Y19") (pinfunction "X1VDD5_Y19") (pintype "passive"))
      (node (ref "L11") (pin "1") (pinfunction "1_1") (pintype "passive"))
      (node (ref "L9") (pin "1") (pinfunction "1_1") (pintype "passive"))
      (node (ref "R10") (pin "1") (pinfunction "1_1") (pintype "passive"))
      (node (ref "R11") (pin "1") (pinfunction "1_1") (pintype "passive"))
    )
    (net (code "34") (name "unconnected-(IC1G-TH_TPA-PadP5)") (class "Default")
      (node (ref "IC1") (pin "P5") (pinfunction "TH_TPA_P5") (pintype "passive+no_connect"))
    )
    (net (code "35") (name "unconnected-(IC1M-NC-PadAA5)") (class "Default")
      (node (ref "IC1") (pin "AA5") (pinfunction "NC_AA5") (pintype "passive+no_connect"))
    )
    (net (code "36") (name "unconnected-(IC1M-NC-PadAA6)") (class "Default")
      (node (ref "IC1") (pin "AA6") (pinfunction "NC_AA6") (pintype "passive+no_connect"))
    )
    (net (code "37") (name "unconnected-(IC1M-NC-PadAA7)") (class "Default")
      (node (ref "IC1") (pin "AA7") (pinfunction "NC_AA7") (pintype "passive+no_connect"))
    )
    (net (code "38") (name "unconnected-(IC1M-NC-PadAA8)") (class "Default")
      (node (ref "IC1") (pin "AA8") (pinfunction "NC_AA8") (pintype "passive+no_connect"))
    )
    (net (code "39") (name "unconnected-(IC1M-NC-PadAA9)") (class "Default")
      (node (ref "IC1") (pin "AA9") (pinfunction "NC_AA9") (pintype "passive+no_connect"))
    )
    (net (code "40") (name "unconnected-(IC1M-NC-PadAA10)") (class "Default")
      (node (ref "IC1") (pin "AA10") (pinfunction "NC_AA10") (pintype "passive+no_connect"))
    )
    (net (code "41") (name "unconnected-(IC1M-NC-PadAA11)") (class "Default")
      (node (ref "IC1") (pin "AA11") (pinfunction "NC_AA11") (pintype "passive+no_connect"))
    )
    (net (code "42") (name "unconnected-(IC1M-NC-PadAA12)") (class "Default")
      (node (ref "IC1") (pin "AA12") (pinfunction "NC_AA12") (pintype "passive+no_connect"))
    )
    (net (code "43") (name "unconnected-(IC1M-NC-PadAB5)") (class "Default")
      (node (ref "IC1") (pin "AB5") (pinfunction "NC_AB5") (pintype "passive+no_connect"))
    )
    (net (code "44") (name "unconnected-(IC1M-NC-PadAB6)") (class "Default")
      (node (ref "IC1") (pin "AB6") (pinfunction "NC_AB6") (pintype "passive+no_connect"))
    )
    (net (code "45") (name "unconnected-(IC1M-NC-PadAB7)") (class "Default")
      (node (ref "IC1") (pin "AB7") (pinfunction "NC_AB7") (pintype "passive+no_connect"))
    )
    (net (code "46") (name "unconnected-(IC1M-NC-PadAB8)") (class "Default")
      (node (ref "IC1") (pin "AB8") (pinfunction "NC_AB8") (pintype "passive+no_connect"))
    )
    (net (code "47") (name "unconnected-(IC1M-NC-PadAB9)") (class "Default")
      (node (ref "IC1") (pin "AB9") (pinfunction "NC_AB9") (pintype "passive+no_connect"))
    )
    (net (code "48") (name "unconnected-(IC1M-NC-PadAB10)") (class "Default")
      (node (ref "IC1") (pin "AB10") (pinfunction "NC_AB10") (pintype "passive+no_connect"))
    )
    (net (code "49") (name "unconnected-(IC1M-NC-PadAB11)") (class "Default")
      (node (ref "IC1") (pin "AB11") (pinfunction "NC_AB11") (pintype "passive+no_connect"))
    )
    (net (code "50") (name "unconnected-(IC1M-NC-PadAB12)") (class "Default")
      (node (ref "IC1") (pin "AB12") (pinfunction "NC_AB12") (pintype "passive+no_connect"))
    )
    (net (code "51") (name "unconnected-(IC1M-NC-PadAC5)") (class "Default")
      (node (ref "IC1") (pin "AC5") (pinfunction "NC_AC5") (pintype "passive+no_connect"))
    )
    (net (code "52") (name "unconnected-(IC1M-NC-PadAC6)") (class "Default")
      (node (ref "IC1") (pin "AC6") (pinfunction "NC_AC6") (pintype "passive+no_connect"))
    )
    (net (code "53") (name "unconnected-(IC1M-NC-PadAC7)") (class "Default")
      (node (ref "IC1") (pin "AC7") (pinfunction "NC_AC7") (pintype "passive+no_connect"))
    )
    (net (code "54") (name "unconnected-(IC1M-NC-PadAC8)") (class "Default")
      (node (ref "IC1") (pin "AC8") (pinfunction "NC_AC8") (pintype "passive+no_connect"))
    )
    (net (code "55") (name "unconnected-(IC1M-NC-PadAC9)") (class "Default")
      (node (ref "IC1") (pin "AC9") (pinfunction "NC_AC9") (pintype "passive+no_connect"))
    )
    (net (code "56") (name "unconnected-(IC1M-NC-PadAC10)") (class "Default")
      (node (ref "IC1") (pin "AC10") (pinfunction "NC_AC10") (pintype "passive+no_connect"))
    )
    (net (code "57") (name "unconnected-(IC1M-NC-PadAC11)") (class "Default")
      (node (ref "IC1") (pin "AC11") (pinfunction "NC_AC11") (pintype "passive+no_connect"))
    )
    (net (code "58") (name "unconnected-(IC1M-NC-PadAC12)") (class "Default")
      (node (ref "IC1") (pin "AC12") (pinfunction "NC_AC12") (pintype "passive+no_connect"))
    )
    (net (code "59") (name "unconnected-(IC1M-NC-PadAD5)") (class "Default")
      (node (ref "IC1") (pin "AD5") (pinfunction "NC_AD5") (pintype "passive+no_connect"))
    )
    (net (code "60") (name "unconnected-(IC1M-NC-PadAD6)") (class "Default")
      (node (ref "IC1") (pin "AD6") (pinfunction "NC_AD6") (pintype "passive+no_connect"))
    )
    (net (code "61") (name "unconnected-(IC1M-NC-PadAD7)") (class "Default")
      (node (ref "IC1") (pin "AD7") (pinfunction "NC_AD7") (pintype "passive+no_connect"))
    )
    (net (code "62") (name "unconnected-(IC1M-NC-PadAD8)") (class "Default")
      (node (ref "IC1") (pin "AD8") (pinfunction "NC_AD8") (pintype "passive+no_connect"))
    )
    (net (code "63") (name "unconnected-(IC1M-NC-PadAD9)") (class "Default")
      (node (ref "IC1") (pin "AD9") (pinfunction "NC_AD9") (pintype "passive+no_connect"))
    )
    (net (code "64") (name "unconnected-(IC1M-NC-PadAD10)") (class "Default")
      (node (ref "IC1") (pin "AD10") (pinfunction "NC_AD10") (pintype "passive+no_connect"))
    )
    (net (code "65") (name "unconnected-(IC1M-NC-PadAD11)") (class "Default")
      (node (ref "IC1") (pin "AD11") (pinfunction "NC_AD11") (pintype "passive+no_connect"))
    )
    (net (code "66") (name "unconnected-(IC1M-NC-PadAD12)") (class "Default")
      (node (ref "IC1") (pin "AD12") (pinfunction "NC_AD12") (pintype "passive+no_connect"))
    )
    (net (code "67") (name "unconnected-(IC1M-NC-PadAE5)") (class "Default")
      (node (ref "IC1") (pin "AE5") (pinfunction "NC_AE5") (pintype "passive+no_connect"))
    )
    (net (code "68") (name "unconnected-(IC1M-NC-PadAE6)") (class "Default")
      (node (ref "IC1") (pin "AE6") (pinfunction "NC_AE6") (pintype "passive+no_connect"))
    )
    (net (code "69") (name "unconnected-(IC1M-NC-PadAE7)") (class "Default")
      (node (ref "IC1") (pin "AE7") (pinfunction "NC_AE7") (pintype "passive+no_connect"))
    )
    (net (code "70") (name "unconnected-(IC1M-NC-PadAE8)") (class "Default")
      (node (ref "IC1") (pin "AE8") (pinfunction "NC_AE8") (pintype "passive+no_connect"))
    )
    (net (code "71") (name "unconnected-(IC1M-NC-PadAE9)") (class "Default")
      (node (ref "IC1") (pin "AE9") (pinfunction "NC_AE9") (pintype "passive+no_connect"))
    )
    (net (code "72") (name "unconnected-(IC1M-NC-PadAE10)") (class "Default")
      (node (ref "IC1") (pin "AE10") (pinfunction "NC_AE10") (pintype "passive+no_connect"))
    )
    (net (code "73") (name "unconnected-(IC1M-NC-PadAE11)") (class "Default")
      (node (ref "IC1") (pin "AE11") (pinfunction "NC_AE11") (pintype "passive+no_connect"))
    )
    (net (code "74") (name "unconnected-(IC1M-NC-PadAE12)") (class "Default")
      (node (ref "IC1") (pin "AE12") (pinfunction "NC_AE12") (pintype "passive+no_connect"))
    )
    (net (code "75") (name "unconnected-(IC1M-NC-PadK6)") (class "Default")
      (node (ref "IC1") (pin "K6") (pinfunction "NC_K6") (pintype "passive+no_connect"))
    )
    (net (code "76") (name "unconnected-(IC1M-NC-PadL6)") (class "Default")
      (node (ref "IC1") (pin "L6") (pinfunction "NC_L6") (pintype "passive+no_connect"))
    )
    (net (code "77") (name "unconnected-(IC1M-NC-PadM6)") (class "Default")
      (node (ref "IC1") (pin "M6") (pinfunction "NC_M6") (pintype "passive+no_connect"))
    )
    (net (code "78") (name "unconnected-(IC1M-NC-PadY7)") (class "Default")
      (node (ref "IC1") (pin "Y7") (pinfunction "NC_Y7") (pintype "passive+no_connect"))
    )
    (net (code "79") (name "unconnected-(IC1M-NC-PadY13)") (class "Default")
      (node (ref "IC1") (pin "Y13") (pinfunction "NC_Y13") (pintype "passive+no_connect"))
    )
  )
)
